# Ai-Camera.net
KiCad netlist of a schematic drawn in EasyEDA Pro
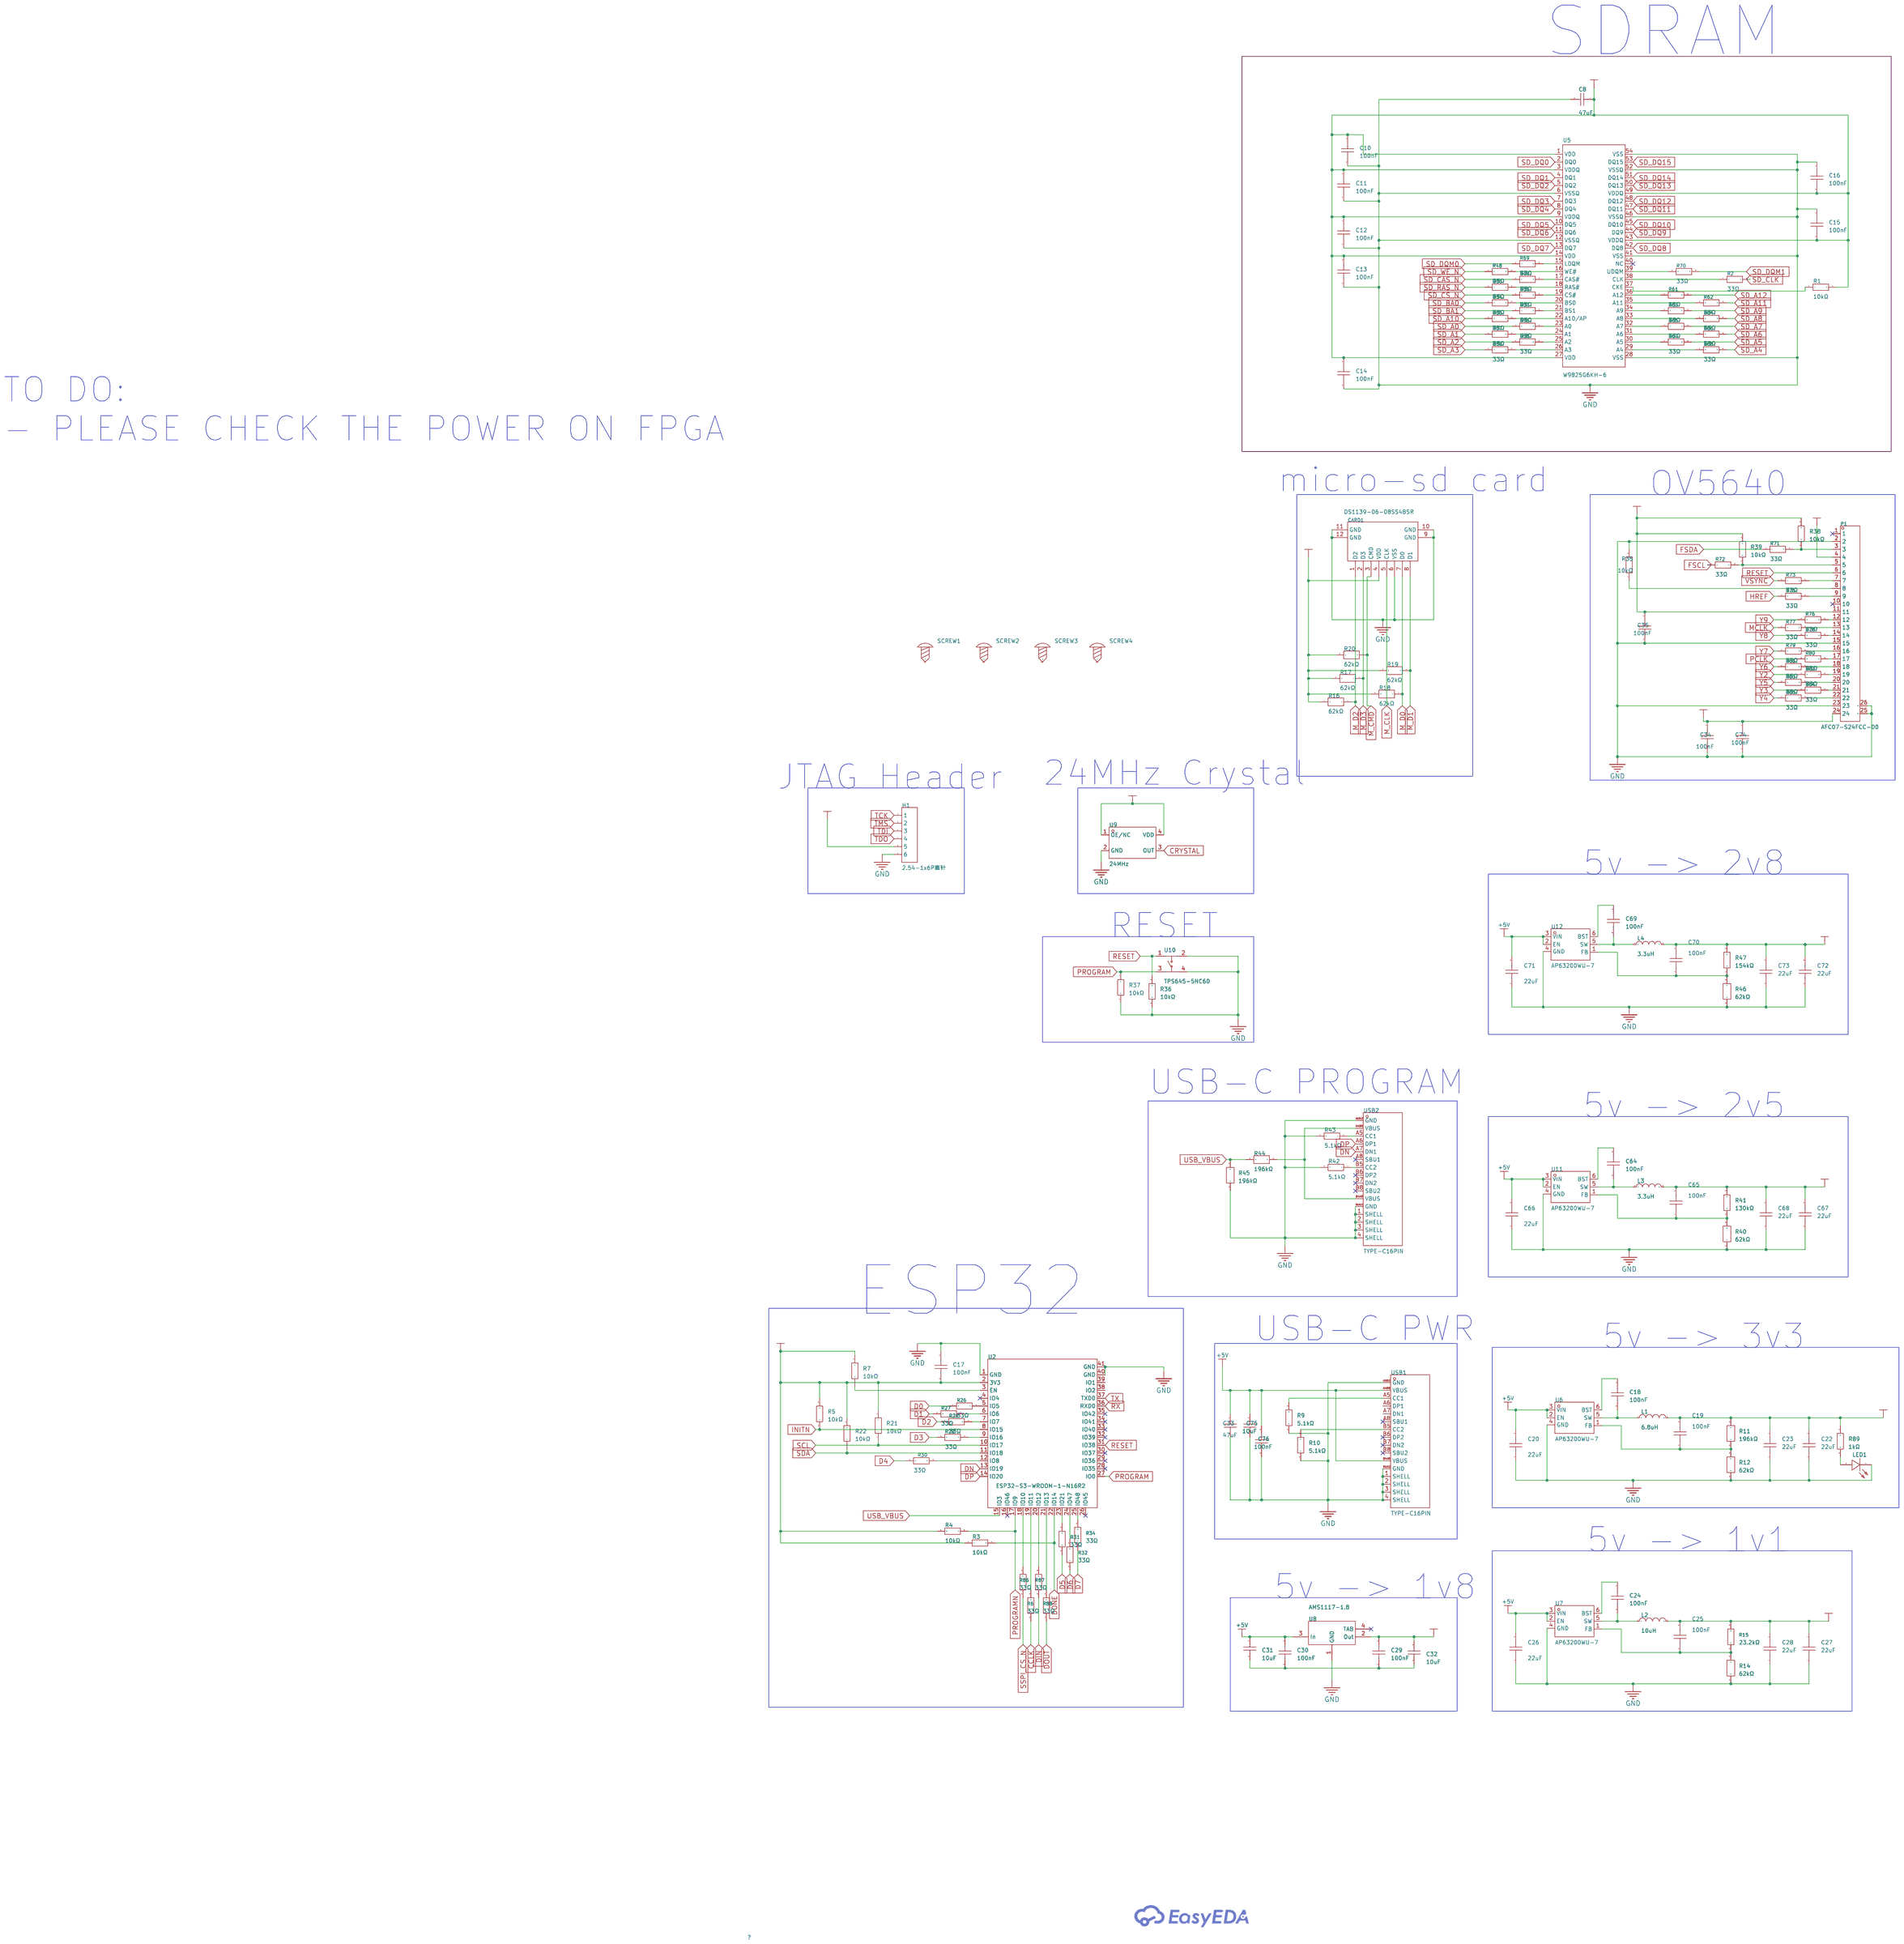
[diagram p0: P1]
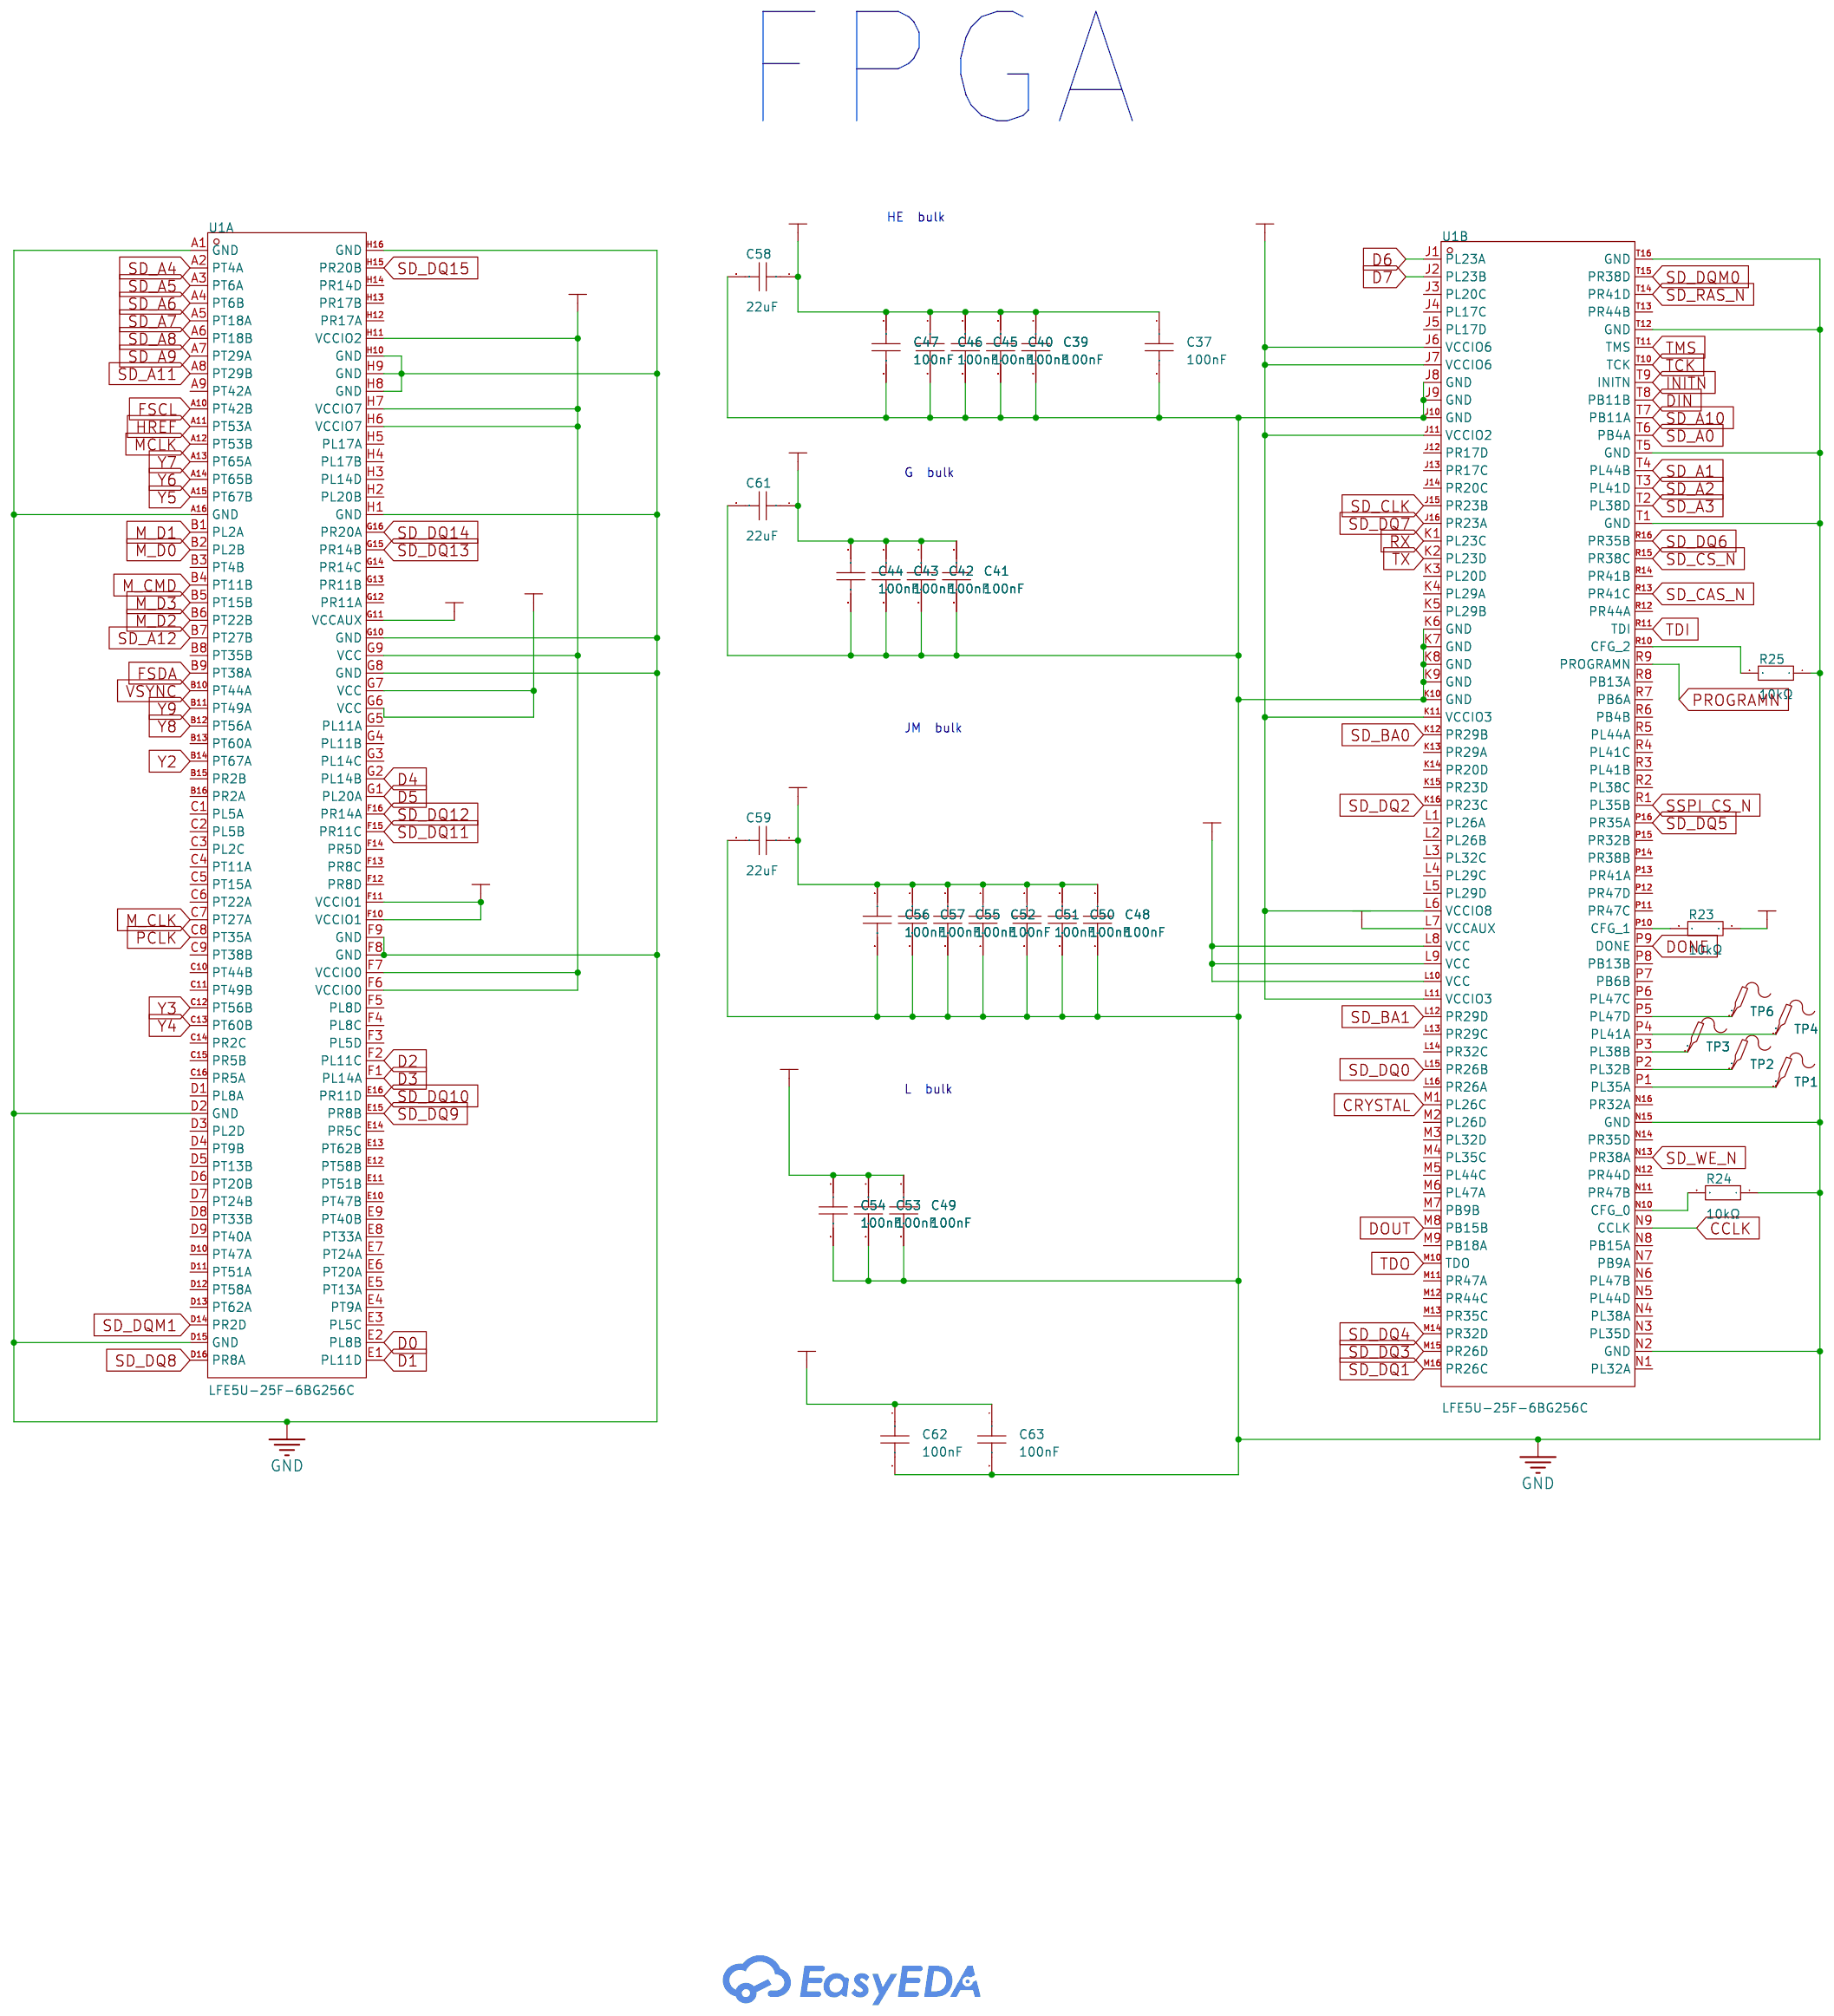
[diagram p1: FPGA]

(export (version "E")
  (design (tool "Eeschema 10.0.6"))
  (components
    (comp (ref "C8")
      (value "47uF")
      (footprint "easyedapro:C0805")
      (description "Capacitance:47uF Tolerance:±20% Tolerance:±20% Voltage Rating:6.3V Temperature Coefficient:X5R")
      (fields
        (field (name "Manufacturer Part") "CL21A476MQYNNNE")
        (field (name "Manufacturer") "SAMSUNG(三星)")
      )
      (libsource (lib "easyedapro") (part "CL21A476MQYNNNE"))
    )
    (comp (ref "C10")
      (value "100nF")
      (footprint "easyedapro:C01005")
      (description "Capacitance:100nF Tolerance:±10% Tolerance:±10% Voltage Rating:6.3V Temperature Coefficient:X5R")
      (fields
        (field (name "Manufacturer Part") "GRM022R60J104KE15D")
        (field (name "Manufacturer") "muRata(村田)")
      )
      (libsource (lib "easyedapro") (part "GRM022R60J104KE15D"))
    )
    (comp (ref "C11")
      (value "100nF")
      (footprint "easyedapro:C01005")
      (description "Capacitance:100nF Tolerance:±10% Tolerance:±10% Voltage Rating:6.3V Temperature Coefficient:X5R")
      (fields
        (field (name "Manufacturer Part") "GRM022R60J104KE15D")
        (field (name "Manufacturer") "muRata(村田)")
      )
      (libsource (lib "easyedapro") (part "GRM022R60J104KE15D"))
    )
    (comp (ref "C12")
      (value "100nF")
      (footprint "easyedapro:C01005")
      (description "Capacitance:100nF Tolerance:±10% Tolerance:±10% Voltage Rating:6.3V Temperature Coefficient:X5R")
      (fields
        (field (name "Manufacturer Part") "GRM022R60J104KE15D")
        (field (name "Manufacturer") "muRata(村田)")
      )
      (libsource (lib "easyedapro") (part "GRM022R60J104KE15D"))
    )
    (comp (ref "C13")
      (value "100nF")
      (footprint "easyedapro:C01005")
      (description "Capacitance:100nF Tolerance:±10% Tolerance:±10% Voltage Rating:6.3V Temperature Coefficient:X5R")
      (fields
        (field (name "Manufacturer Part") "GRM022R60J104KE15D")
        (field (name "Manufacturer") "muRata(村田)")
      )
      (libsource (lib "easyedapro") (part "GRM022R60J104KE15D"))
    )
    (comp (ref "C14")
      (value "100nF")
      (footprint "easyedapro:C01005")
      (description "Capacitance:100nF Tolerance:±10% Tolerance:±10% Voltage Rating:6.3V Temperature Coefficient:X5R")
      (fields
        (field (name "Manufacturer Part") "GRM022R60J104KE15D")
        (field (name "Manufacturer") "muRata(村田)")
      )
      (libsource (lib "easyedapro") (part "GRM022R60J104KE15D"))
    )
    (comp (ref "C15")
      (value "100nF")
      (footprint "easyedapro:C01005")
      (description "Capacitance:100nF Tolerance:±10% Tolerance:±10% Voltage Rating:6.3V Temperature Coefficient:X5R")
      (fields
        (field (name "Manufacturer Part") "GRM022R60J104KE15D")
        (field (name "Manufacturer") "muRata(村田)")
      )
      (libsource (lib "easyedapro") (part "GRM022R60J104KE15D"))
    )
    (comp (ref "C16")
      (value "100nF")
      (footprint "easyedapro:C01005")
      (description "Capacitance:100nF Tolerance:±10% Tolerance:±10% Voltage Rating:6.3V Temperature Coefficient:X5R")
      (fields
        (field (name "Manufacturer Part") "GRM022R60J104KE15D")
        (field (name "Manufacturer") "muRata(村田)")
      )
      (libsource (lib "easyedapro") (part "GRM022R60J104KE15D"))
    )
    (comp (ref "C17")
      (value "100nF")
      (footprint "easyedapro:C01005")
      (description "Capacitance:100nF Tolerance:±10% Tolerance:±10% Voltage Rating:6.3V Temperature Coefficient:X5R")
      (fields
        (field (name "Manufacturer Part") "GRM022R60J104KE15D")
        (field (name "Manufacturer") "muRata(村田)")
      )
      (libsource (lib "easyedapro") (part "GRM022R60J104KE15D"))
    )
    (comp (ref "C18")
      (value "100nF")
      (footprint "easyedapro:C01005")
      (description "Capacitance:100nF Tolerance:±10% Tolerance:±10% Voltage Rating:6.3V Temperature Coefficient:X5R")
      (fields
        (field (name "Manufacturer Part") "GRM022R60J104KE15D")
        (field (name "Manufacturer") "muRata(村田)")
      )
      (libsource (lib "easyedapro") (part "GRM022R60J104KE15D"))
    )
    (comp (ref "C19")
      (value "100nF")
      (footprint "easyedapro:C0603")
      (description "Capacitance:100nF Tolerance:±10% Tolerance:±10% Voltage Rating:50V Temperature Coefficient:X7R")
      (fields
        (field (name "Manufacturer Part") "TCC0603X7R104K500CT")
        (field (name "Manufacturer") "CCTC(三环)")
      )
      (libsource (lib "easyedapro") (part "TCC0603X7R104K500CT"))
    )
    (comp (ref "C20")
      (value "22uF")
      (footprint "easyedapro:C0603")
      (description "Capacitance:22uF Tolerance:±20% Tolerance:±20% Voltage Rating:6.3V Temperature Coefficient:X5R")
      (fields
        (field (name "Manufacturer Part") "TCC0603X5R226M6R3CT")
        (field (name "Manufacturer") "CCTC(三环)")
      )
      (libsource (lib "easyedapro") (part "TCC0603X5R226M6R3CT"))
    )
    (comp (ref "C22")
      (value "22uF")
      (footprint "easyedapro:C0603")
      (description "Capacitance:22uF Tolerance:±20% Tolerance:±20% Voltage Rating:6.3V Temperature Coefficient:X5R")
      (fields
        (field (name "Manufacturer Part") "TCC0603X5R226M6R3CT")
        (field (name "Manufacturer") "CCTC(三环)")
      )
      (libsource (lib "easyedapro") (part "TCC0603X5R226M6R3CT"))
    )
    (comp (ref "C23")
      (value "22uF")
      (footprint "easyedapro:C0603")
      (description "Capacitance:22uF Tolerance:±20% Tolerance:±20% Voltage Rating:6.3V Temperature Coefficient:X5R")
      (fields
        (field (name "Manufacturer Part") "TCC0603X5R226M6R3CT")
        (field (name "Manufacturer") "CCTC(三环)")
      )
      (libsource (lib "easyedapro") (part "TCC0603X5R226M6R3CT"))
    )
    (comp (ref "C24")
      (value "100nF")
      (footprint "easyedapro:C01005")
      (description "Capacitance:100nF Tolerance:±10% Tolerance:±10% Voltage Rating:6.3V Temperature Coefficient:X5R")
      (fields
        (field (name "Manufacturer Part") "GRM022R60J104KE15D")
        (field (name "Manufacturer") "muRata(村田)")
      )
      (libsource (lib "easyedapro") (part "GRM022R60J104KE15D"))
    )
    (comp (ref "C25")
      (value "100nF")
      (footprint "easyedapro:C0603")
      (description "Capacitance:100nF Tolerance:±10% Tolerance:±10% Voltage Rating:50V Temperature Coefficient:X7R")
      (fields
        (field (name "Manufacturer Part") "TCC0603X7R104K500CT")
        (field (name "Manufacturer") "CCTC(三环)")
      )
      (libsource (lib "easyedapro") (part "TCC0603X7R104K500CT"))
    )
    (comp (ref "C26")
      (value "22uF")
      (footprint "easyedapro:C0603")
      (description "Capacitance:22uF Tolerance:±20% Tolerance:±20% Voltage Rating:6.3V Temperature Coefficient:X5R")
      (fields
        (field (name "Manufacturer Part") "TCC0603X5R226M6R3CT")
        (field (name "Manufacturer") "CCTC(三环)")
      )
      (libsource (lib "easyedapro") (part "TCC0603X5R226M6R3CT"))
    )
    (comp (ref "C27")
      (value "22uF")
      (footprint "easyedapro:C0603")
      (description "Capacitance:22uF Tolerance:±20% Tolerance:±20% Voltage Rating:6.3V Temperature Coefficient:X5R")
      (fields
        (field (name "Manufacturer Part") "TCC0603X5R226M6R3CT")
        (field (name "Manufacturer") "CCTC(三环)")
      )
      (libsource (lib "easyedapro") (part "TCC0603X5R226M6R3CT"))
    )
    (comp (ref "C28")
      (value "22uF")
      (footprint "easyedapro:C0603")
      (description "Capacitance:22uF Tolerance:±20% Tolerance:±20% Voltage Rating:6.3V Temperature Coefficient:X5R")
      (fields
        (field (name "Manufacturer Part") "TCC0603X5R226M6R3CT")
        (field (name "Manufacturer") "CCTC(三环)")
      )
      (libsource (lib "easyedapro") (part "TCC0603X5R226M6R3CT"))
    )
    (comp (ref "C29")
      (value "100nF")
      (footprint "easyedapro:C01005")
      (description "Capacitance:100nF Tolerance:±10% Tolerance:±10% Voltage Rating:6.3V Temperature Coefficient:X5R")
      (fields
        (field (name "Manufacturer Part") "GRM022R60J104KE15D")
        (field (name "Manufacturer") "muRata(村田)")
      )
      (libsource (lib "easyedapro") (part "GRM022R60J104KE15D"))
    )
    (comp (ref "C30")
      (value "100nF")
      (footprint "easyedapro:C01005")
      (description "Capacitance:100nF Tolerance:±10% Tolerance:±10% Voltage Rating:6.3V Temperature Coefficient:X5R")
      (fields
        (field (name "Manufacturer Part") "GRM022R60J104KE15D")
        (field (name "Manufacturer") "muRata(村田)")
      )
      (libsource (lib "easyedapro") (part "GRM022R60J104KE15D"))
    )
    (comp (ref "C31")
      (value "10uF")
      (footprint "easyedapro:C0402")
      (description "Capacitance:10uF Tolerance:±20% Tolerance:±20% Voltage Rating:6.3V Temperature Coefficient:X5R")
      (fields
        (field (name "Manufacturer Part") "GRM155R60J106ME44D")
        (field (name "Manufacturer") "muRata(村田)")
      )
      (libsource (lib "easyedapro") (part "GRM155R60J106ME44D"))
    )
    (comp (ref "C32")
      (value "10uF")
      (footprint "easyedapro:C0402")
      (description "Capacitance:10uF Tolerance:±20% Tolerance:±20% Voltage Rating:6.3V Temperature Coefficient:X5R")
      (fields
        (field (name "Manufacturer Part") "GRM155R60J106ME44D")
        (field (name "Manufacturer") "muRata(村田)")
      )
      (libsource (lib "easyedapro") (part "GRM155R60J106ME44D"))
    )
    (comp (ref "C33")
      (value "47uF")
      (footprint "easyedapro:C0805")
      (description "Capacitance:47uF Tolerance:±20% Tolerance:±20% Voltage Rating:6.3V Temperature Coefficient:X5R")
      (fields
        (field (name "Manufacturer Part") "CL21A476MQYNNNE")
        (field (name "Manufacturer") "SAMSUNG(三星)")
      )
      (libsource (lib "easyedapro") (part "CL21A476MQYNNNE"))
    )
    (comp (ref "C34")
      (value "100nF")
      (footprint "easyedapro:C01005")
      (description "Capacitance:100nF Tolerance:±10% Tolerance:±10% Voltage Rating:6.3V Temperature Coefficient:X5R")
      (fields
        (field (name "Manufacturer Part") "GRM022R60J104KE15D")
        (field (name "Manufacturer") "muRata(村田)")
      )
      (libsource (lib "easyedapro") (part "GRM022R60J104KE15D"))
    )
    (comp (ref "C35")
      (value "100nF")
      (footprint "easyedapro:C01005")
      (description "Capacitance:100nF Tolerance:±10% Tolerance:±10% Voltage Rating:6.3V Temperature Coefficient:X5R")
      (fields
        (field (name "Manufacturer Part") "GRM022R60J104KE15D")
        (field (name "Manufacturer") "muRata(村田)")
      )
      (libsource (lib "easyedapro") (part "GRM022R60J104KE15D"))
    )
    (comp (ref "C64")
      (value "100nF")
      (footprint "easyedapro:C01005")
      (description "Capacitance:100nF Tolerance:±10% Tolerance:±10% Voltage Rating:6.3V Temperature Coefficient:X5R")
      (fields
        (field (name "Manufacturer Part") "GRM022R60J104KE15D")
        (field (name "Manufacturer") "muRata(村田)")
      )
      (libsource (lib "easyedapro") (part "GRM022R60J104KE15D"))
    )
    (comp (ref "C65")
      (value "100nF")
      (footprint "easyedapro:C0603")
      (description "Capacitance:100nF Tolerance:±10% Tolerance:±10% Voltage Rating:50V Temperature Coefficient:X7R")
      (fields
        (field (name "Manufacturer Part") "TCC0603X7R104K500CT")
        (field (name "Manufacturer") "CCTC(三环)")
      )
      (libsource (lib "easyedapro") (part "TCC0603X7R104K500CT"))
    )
    (comp (ref "C66")
      (value "22uF")
      (footprint "easyedapro:C0603")
      (description "Capacitance:22uF Tolerance:±20% Tolerance:±20% Voltage Rating:6.3V Temperature Coefficient:X5R")
      (fields
        (field (name "Manufacturer Part") "TCC0603X5R226M6R3CT")
        (field (name "Manufacturer") "CCTC(三环)")
      )
      (libsource (lib "easyedapro") (part "TCC0603X5R226M6R3CT"))
    )
    (comp (ref "C67")
      (value "22uF")
      (footprint "easyedapro:C0603")
      (description "Capacitance:22uF Tolerance:±20% Tolerance:±20% Voltage Rating:6.3V Temperature Coefficient:X5R")
      (fields
        (field (name "Manufacturer Part") "TCC0603X5R226M6R3CT")
        (field (name "Manufacturer") "CCTC(三环)")
      )
      (libsource (lib "easyedapro") (part "TCC0603X5R226M6R3CT"))
    )
    (comp (ref "C68")
      (value "22uF")
      (footprint "easyedapro:C0603")
      (description "Capacitance:22uF Tolerance:±20% Tolerance:±20% Voltage Rating:6.3V Temperature Coefficient:X5R")
      (fields
        (field (name "Manufacturer Part") "TCC0603X5R226M6R3CT")
        (field (name "Manufacturer") "CCTC(三环)")
      )
      (libsource (lib "easyedapro") (part "TCC0603X5R226M6R3CT"))
    )
    (comp (ref "C69")
      (value "100nF")
      (footprint "easyedapro:C01005")
      (description "Capacitance:100nF Tolerance:±10% Tolerance:±10% Voltage Rating:6.3V Temperature Coefficient:X5R")
      (fields
        (field (name "Manufacturer Part") "GRM022R60J104KE15D")
        (field (name "Manufacturer") "muRata(村田)")
      )
      (libsource (lib "easyedapro") (part "GRM022R60J104KE15D"))
    )
    (comp (ref "C70")
      (value "100nF")
      (footprint "easyedapro:C0603")
      (description "Capacitance:100nF Tolerance:±10% Tolerance:±10% Voltage Rating:50V Temperature Coefficient:X7R")
      (fields
        (field (name "Manufacturer Part") "TCC0603X7R104K500CT")
        (field (name "Manufacturer") "CCTC(三环)")
      )
      (libsource (lib "easyedapro") (part "TCC0603X7R104K500CT"))
    )
    (comp (ref "C71")
      (value "22uF")
      (footprint "easyedapro:C0603")
      (description "Capacitance:22uF Tolerance:±20% Tolerance:±20% Voltage Rating:6.3V Temperature Coefficient:X5R")
      (fields
        (field (name "Manufacturer Part") "TCC0603X5R226M6R3CT")
        (field (name "Manufacturer") "CCTC(三环)")
      )
      (libsource (lib "easyedapro") (part "TCC0603X5R226M6R3CT"))
    )
    (comp (ref "C72")
      (value "22uF")
      (footprint "easyedapro:C0603")
      (description "Capacitance:22uF Tolerance:±20% Tolerance:±20% Voltage Rating:6.3V Temperature Coefficient:X5R")
      (fields
        (field (name "Manufacturer Part") "TCC0603X5R226M6R3CT")
        (field (name "Manufacturer") "CCTC(三环)")
      )
      (libsource (lib "easyedapro") (part "TCC0603X5R226M6R3CT"))
    )
    (comp (ref "C73")
      (value "22uF")
      (footprint "easyedapro:C0603")
      (description "Capacitance:22uF Tolerance:±20% Tolerance:±20% Voltage Rating:6.3V Temperature Coefficient:X5R")
      (fields
        (field (name "Manufacturer Part") "TCC0603X5R226M6R3CT")
        (field (name "Manufacturer") "CCTC(三环)")
      )
      (libsource (lib "easyedapro") (part "TCC0603X5R226M6R3CT"))
    )
    (comp (ref "C74")
      (value "100nF")
      (footprint "easyedapro:C01005")
      (description "Capacitance:100nF Tolerance:±10% Tolerance:±10% Voltage Rating:6.3V Temperature Coefficient:X5R")
      (fields
        (field (name "Manufacturer Part") "GRM022R60J104KE15D")
        (field (name "Manufacturer") "muRata(村田)")
      )
      (libsource (lib "easyedapro") (part "GRM022R60J104KE15D"))
    )
    (comp (ref "C75")
      (value "10uF")
      (footprint "easyedapro:C0402")
      (description "Capacitance:10uF Tolerance:±20% Tolerance:±20% Voltage Rating:6.3V Temperature Coefficient:X5R")
      (fields
        (field (name "Manufacturer Part") "GRM155R60J106ME44D")
        (field (name "Manufacturer") "muRata(村田)")
      )
      (libsource (lib "easyedapro") (part "GRM155R60J106ME44D"))
    )
    (comp (ref "C76")
      (value "100nF")
      (footprint "easyedapro:C01005")
      (description "Capacitance:100nF Tolerance:±10% Tolerance:±10% Voltage Rating:6.3V Temperature Coefficient:X5R")
      (fields
        (field (name "Manufacturer Part") "GRM022R60J104KE15D")
        (field (name "Manufacturer") "muRata(村田)")
      )
      (libsource (lib "easyedapro") (part "GRM022R60J104KE15D"))
    )
    (comp (ref "CARD1")
      (value "DS1139-06-08SS4BSR")
      (footprint "easyedapro:TF-SMD_DS1139-06-08SS4BSR")
      (fields (field (name "Manufacturer") "CONNFLY"))
      (libsource (lib "easyedapro") (part "DS1139-06-08SS4BSR"))
    )
    (comp (ref "H1")
      (value "2.54-1x6P直针")
      (footprint "easyedapro:HDR-TH_6P-P2.54-V-M-1")
      (fields (field (name "Manufacturer") "BOOMELE(博穆精密)"))
      (libsource (lib "easyedapro") (part "Header-Male-2.54_1x6"))
    )
    (comp (ref "L1")
      (value "6.8uH")
      (footprint "easyedapro:IND-SMD_L7.0-W6.6")
      (fields (field (name "Manufacturer Part") "FXL0630-6R8-M") (field (name "Manufacturer") "cjiang(长江微电)"))
      (libsource (lib "easyedapro") (part "FXL0630-6R8-M"))
    )
    (comp (ref "L2")
      (value "10uH")
      (footprint "easyedapro:IND-SMD_L7.3-W6.8")
      (fields (field (name "Manufacturer Part") "FXL0630-100-M") (field (name "Manufacturer") "cjiang(长江微电)"))
      (libsource (lib "easyedapro") (part "FXL0630-100-M"))
    )
    (comp (ref "L3")
      (value "3.3uH")
      (footprint "easyedapro:IND-SMD_L4.5-W4.1_SL0420")
      (description "Inductance:3.3uH Tolerance:±20% Tolerance:±20% Current Rating:3.5A Current - Saturation (Isat):4A")
      (fields (field (name "Manufacturer Part") "SL0420-3R3M") (field (name "Manufacturer") "台湾陆海"))
      (libsource (lib "easyedapro") (part "SL0420-3R3M"))
    )
    (comp (ref "L4")
      (value "3.3uH")
      (footprint "easyedapro:IND-SMD_L4.5-W4.1_SL0420")
      (description "Inductance:3.3uH Tolerance:±20% Tolerance:±20% Current Rating:3.5A Current - Saturation (Isat):4A")
      (fields (field (name "Manufacturer Part") "SL0420-3R3M") (field (name "Manufacturer") "台湾陆海"))
      (libsource (lib "easyedapro") (part "SL0420-3R3M"))
    )
    (comp (ref "LED1")
      (value "~")
      (footprint "easyedapro:LED0805-RD_RED")
      (description "Emitted Color:红灯")
      (fields (field (name "Manufacturer Part") "NCD0805R1") (field (name "Manufacturer") "国星光电"))
      (libsource (lib "easyedapro") (part "FC-2012HRK-620D"))
    )
    (comp (ref "P1")
      (value "AFC07-S24FCC-00")
      (footprint "easyedapro:FPC-SMD_AFC07-S24FCC-00")
      (fields (field (name "Manufacturer") "JS(钜硕电子)"))
      (libsource (lib "easyedapro") (part "FPC 0.5MM 24P Pull type H2.0mm Under the next"))
    )
    (comp (ref "R1")
      (value "10kΩ")
      (footprint "easyedapro:R0402")
      (fields
        (field (name "Manufacturer Part") "0402WGF1002TCE")
        (field (name "Manufacturer") "UNI-ROYAL(厚声)")
      )
      (libsource (lib "easyedapro") (part "0402WGF1002TCE"))
    )
    (comp (ref "R2")
      (value "33Ω")
      (footprint "easyedapro:R0402")
      (fields
        (field (name "Manufacturer Part") "0402WGF330JTCE")
        (field (name "Manufacturer") "UNI-ROYAL(厚声)")
      )
      (libsource (lib "easyedapro") (part "0402WGF330JTCE"))
    )
    (comp (ref "R3")
      (value "10kΩ")
      (footprint "easyedapro:R0402")
      (fields
        (field (name "Manufacturer Part") "0402WGF1002TCE")
        (field (name "Manufacturer") "UNI-ROYAL(厚声)")
      )
      (libsource (lib "easyedapro") (part "0402WGF1002TCE"))
    )
    (comp (ref "R4")
      (value "10kΩ")
      (footprint "easyedapro:R0402")
      (fields
        (field (name "Manufacturer Part") "0402WGF1002TCE")
        (field (name "Manufacturer") "UNI-ROYAL(厚声)")
      )
      (libsource (lib "easyedapro") (part "0402WGF1002TCE"))
    )
    (comp (ref "R5")
      (value "10kΩ")
      (footprint "easyedapro:R0402")
      (fields
        (field (name "Manufacturer Part") "0402WGF1002TCE")
        (field (name "Manufacturer") "UNI-ROYAL(厚声)")
      )
      (libsource (lib "easyedapro") (part "0402WGF1002TCE"))
    )
    (comp (ref "R6")
      (value "33Ω")
      (footprint "easyedapro:R0402")
      (fields
        (field (name "Manufacturer Part") "0402WGF330JTCE")
        (field (name "Manufacturer") "UNI-ROYAL(厚声)")
      )
      (libsource (lib "easyedapro") (part "0402WGF330JTCE"))
    )
    (comp (ref "R7")
      (value "10kΩ")
      (footprint "easyedapro:R0402")
      (fields
        (field (name "Manufacturer Part") "0402WGF1002TCE")
        (field (name "Manufacturer") "UNI-ROYAL(厚声)")
      )
      (libsource (lib "easyedapro") (part "0402WGF1002TCE"))
    )
    (comp (ref "R9")
      (value "5.1kΩ")
      (footprint "easyedapro:R0603")
      (fields
        (field (name "Manufacturer Part") "0603WAF5101T5E")
        (field (name "Manufacturer") "UNI-ROYAL(厚声)")
      )
      (libsource (lib "easyedapro") (part "0603WAF5101T5E"))
    )
    (comp (ref "R10")
      (value "5.1kΩ")
      (footprint "easyedapro:R0603")
      (fields
        (field (name "Manufacturer Part") "0603WAF5101T5E")
        (field (name "Manufacturer") "UNI-ROYAL(厚声)")
      )
      (libsource (lib "easyedapro") (part "0603WAF5101T5E"))
    )
    (comp (ref "R11")
      (value "196kΩ")
      (footprint "easyedapro:R0603")
      (fields (field (name "Manufacturer Part") "FRC0603F1963TS") (field (name "Manufacturer") "FOJAN(富捷)"))
      (libsource (lib "easyedapro") (part "FRC0603F1963TS"))
    )
    (comp (ref "R12")
      (value "62kΩ")
      (footprint "easyedapro:R0603")
      (fields (field (name "Manufacturer Part") "FRC0603F6202TS") (field (name "Manufacturer") "FOJAN(富捷)"))
      (libsource (lib "easyedapro") (part "FRC0603F6202TS"))
    )
    (comp (ref "R14")
      (value "62kΩ")
      (footprint "easyedapro:R0603")
      (fields (field (name "Manufacturer Part") "FRC0603F6202TS") (field (name "Manufacturer") "FOJAN(富捷)"))
      (libsource (lib "easyedapro") (part "FRC0603F6202TS"))
    )
    (comp (ref "R15")
      (value "23.2kΩ")
      (footprint "easyedapro:R0603")
      (fields
        (field (name "Manufacturer Part") "0603WAF2322T5E")
        (field (name "Manufacturer") "UNI-ROYAL(厚声)")
      )
      (libsource (lib "easyedapro") (part "0603WAF2322T5E"))
    )
    (comp (ref "R16")
      (value "62kΩ")
      (footprint "easyedapro:R0603")
      (fields (field (name "Manufacturer Part") "FRC0603F6202TS") (field (name "Manufacturer") "FOJAN(富捷)"))
      (libsource (lib "easyedapro") (part "FRC0603F6202TS"))
    )
    (comp (ref "R17")
      (value "62kΩ")
      (footprint "easyedapro:R0603")
      (fields (field (name "Manufacturer Part") "FRC0603F6202TS") (field (name "Manufacturer") "FOJAN(富捷)"))
      (libsource (lib "easyedapro") (part "FRC0603F6202TS"))
    )
    (comp (ref "R18")
      (value "62kΩ")
      (footprint "easyedapro:R0603")
      (fields (field (name "Manufacturer Part") "FRC0603F6202TS") (field (name "Manufacturer") "FOJAN(富捷)"))
      (libsource (lib "easyedapro") (part "FRC0603F6202TS"))
    )
    (comp (ref "R19")
      (value "62kΩ")
      (footprint "easyedapro:R0603")
      (fields (field (name "Manufacturer Part") "FRC0603F6202TS") (field (name "Manufacturer") "FOJAN(富捷)"))
      (libsource (lib "easyedapro") (part "FRC0603F6202TS"))
    )
    (comp (ref "R20")
      (value "62kΩ")
      (footprint "easyedapro:R0603")
      (fields (field (name "Manufacturer Part") "FRC0603F6202TS") (field (name "Manufacturer") "FOJAN(富捷)"))
      (libsource (lib "easyedapro") (part "FRC0603F6202TS"))
    )
    (comp (ref "R21")
      (value "10kΩ")
      (footprint "easyedapro:R0402")
      (fields
        (field (name "Manufacturer Part") "0402WGF1002TCE")
        (field (name "Manufacturer") "UNI-ROYAL(厚声)")
      )
      (libsource (lib "easyedapro") (part "0402WGF1002TCE"))
    )
    (comp (ref "R22")
      (value "10kΩ")
      (footprint "easyedapro:R0402")
      (fields
        (field (name "Manufacturer Part") "0402WGF1002TCE")
        (field (name "Manufacturer") "UNI-ROYAL(厚声)")
      )
      (libsource (lib "easyedapro") (part "0402WGF1002TCE"))
    )
    (comp (ref "R26")
      (value "33Ω")
      (footprint "easyedapro:R0402")
      (fields
        (field (name "Manufacturer Part") "0402WGF330JTCE")
        (field (name "Manufacturer") "UNI-ROYAL(厚声)")
      )
      (libsource (lib "easyedapro") (part "0402WGF330JTCE"))
    )
    (comp (ref "R27")
      (value "33Ω")
      (footprint "easyedapro:R0402")
      (fields
        (field (name "Manufacturer Part") "0402WGF330JTCE")
        (field (name "Manufacturer") "UNI-ROYAL(厚声)")
      )
      (libsource (lib "easyedapro") (part "0402WGF330JTCE"))
    )
    (comp (ref "R28")
      (value "33Ω")
      (footprint "easyedapro:R0402")
      (fields
        (field (name "Manufacturer Part") "0402WGF330JTCE")
        (field (name "Manufacturer") "UNI-ROYAL(厚声)")
      )
      (libsource (lib "easyedapro") (part "0402WGF330JTCE"))
    )
    (comp (ref "R29")
      (value "33Ω")
      (footprint "easyedapro:R0402")
      (fields
        (field (name "Manufacturer Part") "0402WGF330JTCE")
        (field (name "Manufacturer") "UNI-ROYAL(厚声)")
      )
      (libsource (lib "easyedapro") (part "0402WGF330JTCE"))
    )
    (comp (ref "R30")
      (value "33Ω")
      (footprint "easyedapro:R0402")
      (fields
        (field (name "Manufacturer Part") "0402WGF330JTCE")
        (field (name "Manufacturer") "UNI-ROYAL(厚声)")
      )
      (libsource (lib "easyedapro") (part "0402WGF330JTCE"))
    )
    (comp (ref "R31")
      (value "33Ω")
      (footprint "easyedapro:R0402")
      (fields
        (field (name "Manufacturer Part") "0402WGF330JTCE")
        (field (name "Manufacturer") "UNI-ROYAL(厚声)")
      )
      (libsource (lib "easyedapro") (part "0402WGF330JTCE"))
    )
    (comp (ref "R32")
      (value "33Ω")
      (footprint "easyedapro:R0402")
      (fields
        (field (name "Manufacturer Part") "0402WGF330JTCE")
        (field (name "Manufacturer") "UNI-ROYAL(厚声)")
      )
      (libsource (lib "easyedapro") (part "0402WGF330JTCE"))
    )
    (comp (ref "R34")
      (value "33Ω")
      (footprint "easyedapro:R0402")
      (fields
        (field (name "Manufacturer Part") "0402WGF330JTCE")
        (field (name "Manufacturer") "UNI-ROYAL(厚声)")
      )
      (libsource (lib "easyedapro") (part "0402WGF330JTCE"))
    )
    (comp (ref "R35")
      (value "10kΩ")
      (footprint "easyedapro:R0402")
      (fields
        (field (name "Manufacturer Part") "0402WGF1002TCE")
        (field (name "Manufacturer") "UNI-ROYAL(厚声)")
      )
      (libsource (lib "easyedapro") (part "0402WGF1002TCE"))
    )
    (comp (ref "R36")
      (value "10kΩ")
      (footprint "easyedapro:R0402")
      (fields
        (field (name "Manufacturer Part") "0402WGF1002TCE")
        (field (name "Manufacturer") "UNI-ROYAL(厚声)")
      )
      (libsource (lib "easyedapro") (part "0402WGF1002TCE"))
    )
    (comp (ref "R37")
      (value "10kΩ")
      (footprint "easyedapro:R0402")
      (fields
        (field (name "Manufacturer Part") "0402WGF1002TCE")
        (field (name "Manufacturer") "UNI-ROYAL(厚声)")
      )
      (libsource (lib "easyedapro") (part "0402WGF1002TCE"))
    )
    (comp (ref "R38")
      (value "10kΩ")
      (footprint "easyedapro:R0402")
      (fields
        (field (name "Manufacturer Part") "0402WGF1002TCE")
        (field (name "Manufacturer") "UNI-ROYAL(厚声)")
      )
      (libsource (lib "easyedapro") (part "0402WGF1002TCE"))
    )
    (comp (ref "R39")
      (value "10kΩ")
      (footprint "easyedapro:R0402")
      (fields
        (field (name "Manufacturer Part") "0402WGF1002TCE")
        (field (name "Manufacturer") "UNI-ROYAL(厚声)")
      )
      (libsource (lib "easyedapro") (part "0402WGF1002TCE"))
    )
    (comp (ref "R40")
      (value "62kΩ")
      (footprint "easyedapro:R0603")
      (fields (field (name "Manufacturer Part") "FRC0603F6202TS") (field (name "Manufacturer") "FOJAN(富捷)"))
      (libsource (lib "easyedapro") (part "FRC0603F6202TS"))
    )
    (comp (ref "R41")
      (value "130kΩ")
      (footprint "easyedapro:R0402")
      (fields (field (name "Manufacturer Part") "RC0402FR-07130KL") (field (name "Manufacturer") "YAGEO(国巨)"))
      (libsource (lib "easyedapro") (part "RC0402FR-07130KL"))
    )
    (comp (ref "R42")
      (value "5.1kΩ")
      (footprint "easyedapro:R0603")
      (fields
        (field (name "Manufacturer Part") "0603WAF5101T5E")
        (field (name "Manufacturer") "UNI-ROYAL(厚声)")
      )
      (libsource (lib "easyedapro") (part "0603WAF5101T5E"))
    )
    (comp (ref "R43")
      (value "5.1kΩ")
      (footprint "easyedapro:R0603")
      (fields
        (field (name "Manufacturer Part") "0603WAF5101T5E")
        (field (name "Manufacturer") "UNI-ROYAL(厚声)")
      )
      (libsource (lib "easyedapro") (part "0603WAF5101T5E"))
    )
    (comp (ref "R44")
      (value "196kΩ")
      (footprint "easyedapro:R0603")
      (fields (field (name "Manufacturer Part") "FRC0603F1963TS") (field (name "Manufacturer") "FOJAN(富捷)"))
      (libsource (lib "easyedapro") (part "FRC0603F1963TS"))
    )
    (comp (ref "R45")
      (value "196kΩ")
      (footprint "easyedapro:R0603")
      (fields (field (name "Manufacturer Part") "FRC0603F1963TS") (field (name "Manufacturer") "FOJAN(富捷)"))
      (libsource (lib "easyedapro") (part "FRC0603F1963TS"))
    )
    (comp (ref "R46")
      (value "62kΩ")
      (footprint "easyedapro:R0603")
      (fields (field (name "Manufacturer Part") "FRC0603F6202TS") (field (name "Manufacturer") "FOJAN(富捷)"))
      (libsource (lib "easyedapro") (part "FRC0603F6202TS"))
    )
    (comp (ref "R47")
      (value "154kΩ")
      (footprint "easyedapro:R0402")
      (fields
        (field (name "Manufacturer Part") "0402WGF1543TCE")
        (field (name "Manufacturer") "UNI-ROYAL(厚声)")
      )
      (libsource (lib "easyedapro") (part "0402WGF1543TCE"))
    )
    (comp (ref "R48")
      (value "33Ω")
      (footprint "easyedapro:R0402")
      (fields
        (field (name "Manufacturer Part") "0402WGF330JTCE")
        (field (name "Manufacturer") "UNI-ROYAL(厚声)")
      )
      (libsource (lib "easyedapro") (part "0402WGF330JTCE"))
    )
    (comp (ref "R49")
      (value "33Ω")
      (footprint "easyedapro:R0402")
      (fields
        (field (name "Manufacturer Part") "0402WGF330JTCE")
        (field (name "Manufacturer") "UNI-ROYAL(厚声)")
      )
      (libsource (lib "easyedapro") (part "0402WGF330JTCE"))
    )
    (comp (ref "R50")
      (value "33Ω")
      (footprint "easyedapro:R0402")
      (fields
        (field (name "Manufacturer Part") "0402WGF330JTCE")
        (field (name "Manufacturer") "UNI-ROYAL(厚声)")
      )
      (libsource (lib "easyedapro") (part "0402WGF330JTCE"))
    )
    (comp (ref "R51")
      (value "33Ω")
      (footprint "easyedapro:R0402")
      (fields
        (field (name "Manufacturer Part") "0402WGF330JTCE")
        (field (name "Manufacturer") "UNI-ROYAL(厚声)")
      )
      (libsource (lib "easyedapro") (part "0402WGF330JTCE"))
    )
    (comp (ref "R53")
      (value "33Ω")
      (footprint "easyedapro:R0402")
      (fields
        (field (name "Manufacturer Part") "0402WGF330JTCE")
        (field (name "Manufacturer") "UNI-ROYAL(厚声)")
      )
      (libsource (lib "easyedapro") (part "0402WGF330JTCE"))
    )
    (comp (ref "R54")
      (value "33Ω")
      (footprint "easyedapro:R0402")
      (fields
        (field (name "Manufacturer Part") "0402WGF330JTCE")
        (field (name "Manufacturer") "UNI-ROYAL(厚声)")
      )
      (libsource (lib "easyedapro") (part "0402WGF330JTCE"))
    )
    (comp (ref "R55")
      (value "33Ω")
      (footprint "easyedapro:R0402")
      (fields
        (field (name "Manufacturer Part") "0402WGF330JTCE")
        (field (name "Manufacturer") "UNI-ROYAL(厚声)")
      )
      (libsource (lib "easyedapro") (part "0402WGF330JTCE"))
    )
    (comp (ref "R56")
      (value "33Ω")
      (footprint "easyedapro:R0402")
      (fields
        (field (name "Manufacturer Part") "0402WGF330JTCE")
        (field (name "Manufacturer") "UNI-ROYAL(厚声)")
      )
      (libsource (lib "easyedapro") (part "0402WGF330JTCE"))
    )
    (comp (ref "R57")
      (value "33Ω")
      (footprint "easyedapro:R0402")
      (fields
        (field (name "Manufacturer Part") "0402WGF330JTCE")
        (field (name "Manufacturer") "UNI-ROYAL(厚声)")
      )
      (libsource (lib "easyedapro") (part "0402WGF330JTCE"))
    )
    (comp (ref "R58")
      (value "33Ω")
      (footprint "easyedapro:R0402")
      (fields
        (field (name "Manufacturer Part") "0402WGF330JTCE")
        (field (name "Manufacturer") "UNI-ROYAL(厚声)")
      )
      (libsource (lib "easyedapro") (part "0402WGF330JTCE"))
    )
    (comp (ref "R59")
      (value "33Ω")
      (footprint "easyedapro:R0402")
      (fields
        (field (name "Manufacturer Part") "0402WGF330JTCE")
        (field (name "Manufacturer") "UNI-ROYAL(厚声)")
      )
      (libsource (lib "easyedapro") (part "0402WGF330JTCE"))
    )
    (comp (ref "R61")
      (value "33Ω")
      (footprint "easyedapro:R0402")
      (fields
        (field (name "Manufacturer Part") "0402WGF330JTCE")
        (field (name "Manufacturer") "UNI-ROYAL(厚声)")
      )
      (libsource (lib "easyedapro") (part "0402WGF330JTCE"))
    )
    (comp (ref "R62")
      (value "33Ω")
      (footprint "easyedapro:R0402")
      (fields
        (field (name "Manufacturer Part") "0402WGF330JTCE")
        (field (name "Manufacturer") "UNI-ROYAL(厚声)")
      )
      (libsource (lib "easyedapro") (part "0402WGF330JTCE"))
    )
    (comp (ref "R63")
      (value "33Ω")
      (footprint "easyedapro:R0402")
      (fields
        (field (name "Manufacturer Part") "0402WGF330JTCE")
        (field (name "Manufacturer") "UNI-ROYAL(厚声)")
      )
      (libsource (lib "easyedapro") (part "0402WGF330JTCE"))
    )
    (comp (ref "R64")
      (value "33Ω")
      (footprint "easyedapro:R0402")
      (fields
        (field (name "Manufacturer Part") "0402WGF330JTCE")
        (field (name "Manufacturer") "UNI-ROYAL(厚声)")
      )
      (libsource (lib "easyedapro") (part "0402WGF330JTCE"))
    )
    (comp (ref "R65")
      (value "33Ω")
      (footprint "easyedapro:R0402")
      (fields
        (field (name "Manufacturer Part") "0402WGF330JTCE")
        (field (name "Manufacturer") "UNI-ROYAL(厚声)")
      )
      (libsource (lib "easyedapro") (part "0402WGF330JTCE"))
    )
    (comp (ref "R66")
      (value "33Ω")
      (footprint "easyedapro:R0402")
      (fields
        (field (name "Manufacturer Part") "0402WGF330JTCE")
        (field (name "Manufacturer") "UNI-ROYAL(厚声)")
      )
      (libsource (lib "easyedapro") (part "0402WGF330JTCE"))
    )
    (comp (ref "R67")
      (value "33Ω")
      (footprint "easyedapro:R0402")
      (fields
        (field (name "Manufacturer Part") "0402WGF330JTCE")
        (field (name "Manufacturer") "UNI-ROYAL(厚声)")
      )
      (libsource (lib "easyedapro") (part "0402WGF330JTCE"))
    )
    (comp (ref "R68")
      (value "33Ω")
      (footprint "easyedapro:R0402")
      (fields
        (field (name "Manufacturer Part") "0402WGF330JTCE")
        (field (name "Manufacturer") "UNI-ROYAL(厚声)")
      )
      (libsource (lib "easyedapro") (part "0402WGF330JTCE"))
    )
    (comp (ref "R69")
      (value "33Ω")
      (footprint "easyedapro:R0402")
      (fields
        (field (name "Manufacturer Part") "0402WGF330JTCE")
        (field (name "Manufacturer") "UNI-ROYAL(厚声)")
      )
      (libsource (lib "easyedapro") (part "0402WGF330JTCE"))
    )
    (comp (ref "R70")
      (value "33Ω")
      (footprint "easyedapro:R0402")
      (fields
        (field (name "Manufacturer Part") "0402WGF330JTCE")
        (field (name "Manufacturer") "UNI-ROYAL(厚声)")
      )
      (libsource (lib "easyedapro") (part "0402WGF330JTCE"))
    )
    (comp (ref "R71")
      (value "33Ω")
      (footprint "easyedapro:R0402")
      (fields
        (field (name "Manufacturer Part") "0402WGF330JTCE")
        (field (name "Manufacturer") "UNI-ROYAL(厚声)")
      )
      (libsource (lib "easyedapro") (part "0402WGF330JTCE"))
    )
    (comp (ref "R72")
      (value "33Ω")
      (footprint "easyedapro:R0402")
      (fields
        (field (name "Manufacturer Part") "0402WGF330JTCE")
        (field (name "Manufacturer") "UNI-ROYAL(厚声)")
      )
      (libsource (lib "easyedapro") (part "0402WGF330JTCE"))
    )
    (comp (ref "R73")
      (value "33Ω")
      (footprint "easyedapro:R0402")
      (fields
        (field (name "Manufacturer Part") "0402WGF330JTCE")
        (field (name "Manufacturer") "UNI-ROYAL(厚声)")
      )
      (libsource (lib "easyedapro") (part "0402WGF330JTCE"))
    )
    (comp (ref "R75")
      (value "33Ω")
      (footprint "easyedapro:R0402")
      (fields
        (field (name "Manufacturer Part") "0402WGF330JTCE")
        (field (name "Manufacturer") "UNI-ROYAL(厚声)")
      )
      (libsource (lib "easyedapro") (part "0402WGF330JTCE"))
    )
    (comp (ref "R76")
      (value "33Ω")
      (footprint "easyedapro:R0402")
      (fields
        (field (name "Manufacturer Part") "0402WGF330JTCE")
        (field (name "Manufacturer") "UNI-ROYAL(厚声)")
      )
      (libsource (lib "easyedapro") (part "0402WGF330JTCE"))
    )
    (comp (ref "R77")
      (value "33Ω")
      (footprint "easyedapro:R0402")
      (fields
        (field (name "Manufacturer Part") "0402WGF330JTCE")
        (field (name "Manufacturer") "UNI-ROYAL(厚声)")
      )
      (libsource (lib "easyedapro") (part "0402WGF330JTCE"))
    )
    (comp (ref "R78")
      (value "33Ω")
      (footprint "easyedapro:R0402")
      (fields
        (field (name "Manufacturer Part") "0402WGF330JTCE")
        (field (name "Manufacturer") "UNI-ROYAL(厚声)")
      )
      (libsource (lib "easyedapro") (part "0402WGF330JTCE"))
    )
    (comp (ref "R79")
      (value "33Ω")
      (footprint "easyedapro:R0402")
      (fields
        (field (name "Manufacturer Part") "0402WGF330JTCE")
        (field (name "Manufacturer") "UNI-ROYAL(厚声)")
      )
      (libsource (lib "easyedapro") (part "0402WGF330JTCE"))
    )
    (comp (ref "R80")
      (value "33Ω")
      (footprint "easyedapro:R0402")
      (fields
        (field (name "Manufacturer Part") "0402WGF330JTCE")
        (field (name "Manufacturer") "UNI-ROYAL(厚声)")
      )
      (libsource (lib "easyedapro") (part "0402WGF330JTCE"))
    )
    (comp (ref "R81")
      (value "33Ω")
      (footprint "easyedapro:R0402")
      (fields
        (field (name "Manufacturer Part") "0402WGF330JTCE")
        (field (name "Manufacturer") "UNI-ROYAL(厚声)")
      )
      (libsource (lib "easyedapro") (part "0402WGF330JTCE"))
    )
    (comp (ref "R82")
      (value "33Ω")
      (footprint "easyedapro:R0402")
      (fields
        (field (name "Manufacturer Part") "0402WGF330JTCE")
        (field (name "Manufacturer") "UNI-ROYAL(厚声)")
      )
      (libsource (lib "easyedapro") (part "0402WGF330JTCE"))
    )
    (comp (ref "R83")
      (value "33Ω")
      (footprint "easyedapro:R0402")
      (fields
        (field (name "Manufacturer Part") "0402WGF330JTCE")
        (field (name "Manufacturer") "UNI-ROYAL(厚声)")
      )
      (libsource (lib "easyedapro") (part "0402WGF330JTCE"))
    )
    (comp (ref "R84")
      (value "33Ω")
      (footprint "easyedapro:R0402")
      (fields
        (field (name "Manufacturer Part") "0402WGF330JTCE")
        (field (name "Manufacturer") "UNI-ROYAL(厚声)")
      )
      (libsource (lib "easyedapro") (part "0402WGF330JTCE"))
    )
    (comp (ref "R85")
      (value "33Ω")
      (footprint "easyedapro:R0402")
      (fields
        (field (name "Manufacturer Part") "0402WGF330JTCE")
        (field (name "Manufacturer") "UNI-ROYAL(厚声)")
      )
      (libsource (lib "easyedapro") (part "0402WGF330JTCE"))
    )
    (comp (ref "R86")
      (value "33Ω")
      (footprint "easyedapro:R0402")
      (fields
        (field (name "Manufacturer Part") "0402WGF330JTCE")
        (field (name "Manufacturer") "UNI-ROYAL(厚声)")
      )
      (libsource (lib "easyedapro") (part "0402WGF330JTCE"))
    )
    (comp (ref "R87")
      (value "33Ω")
      (footprint "easyedapro:R0402")
      (fields
        (field (name "Manufacturer Part") "0402WGF330JTCE")
        (field (name "Manufacturer") "UNI-ROYAL(厚声)")
      )
      (libsource (lib "easyedapro") (part "0402WGF330JTCE"))
    )
    (comp (ref "R88")
      (value "33Ω")
      (footprint "easyedapro:R0402")
      (fields
        (field (name "Manufacturer Part") "0402WGF330JTCE")
        (field (name "Manufacturer") "UNI-ROYAL(厚声)")
      )
      (libsource (lib "easyedapro") (part "0402WGF330JTCE"))
    )
    (comp (ref "R89")
      (value "1kΩ")
      (footprint "easyedapro:R1206")
      (fields
        (field (name "Manufacturer Part") "1206W4J0102T5E")
        (field (name "Manufacturer") "UNI-ROYAL(厚声)")
      )
      (libsource (lib "easyedapro") (part "1206W4J0102T5E"))
    )
    (comp (ref "SCREW1")
      (value "~")
      (footprint "easyedapro:Screw-Hole-M3")
      (libsource (lib "easyedapro") (part "Screw-Hole"))
    )
    (comp (ref "SCREW2")
      (value "~")
      (footprint "easyedapro:Screw-Hole-M3")
      (libsource (lib "easyedapro") (part "Screw-Hole"))
    )
    (comp (ref "SCREW3")
      (value "~")
      (footprint "easyedapro:Screw-Hole-M3")
      (libsource (lib "easyedapro") (part "Screw-Hole"))
    )
    (comp (ref "SCREW4")
      (value "~")
      (footprint "easyedapro:Screw-Hole-M3")
      (libsource (lib "easyedapro") (part "Screw-Hole"))
    )
    (comp (ref "U2")
      (value "ESP32-S3-WROOM-1-N16R2")
      (footprint "easyedapro:WIRELM-SMD_ESP32-S3-WROOM-1")
      (fields (field (name "Manufacturer") "ESPRESSIF(乐鑫)"))
      (libsource (lib "easyedapro") (part "ESP32-S3-WROOM-1(N16R2)"))
    )
    (comp (ref "U5")
      (value "W9825G6KH-6")
      (footprint "easyedapro:TSOP-54_L22.2-W10.2-P0.80-LS11.8-BL")
      (fields (field (name "Manufacturer") "Winbond(华邦)"))
      (libsource (lib "easyedapro") (part "W9825G6KH-6"))
    )
    (comp (ref "U6")
      (value "AP63200WU-7")
      (footprint "easyedapro:SOT-23-6_L2.9-W1.6-P0.95-LS2.8-BR")
      (fields (field (name "Manufacturer") "DIODES(美台)"))
      (libsource (lib "easyedapro") (part "AP63200WU-7"))
    )
    (comp (ref "U7")
      (value "AP63200WU-7")
      (footprint "easyedapro:SOT-23-6_L2.9-W1.6-P0.95-LS2.8-BR")
      (fields (field (name "Manufacturer") "DIODES(美台)"))
      (libsource (lib "easyedapro") (part "AP63200WU-7"))
    )
    (comp (ref "U8")
      (value "AMS1117-1.8")
      (footprint "easyedapro:SOT-223-4_L6.5-W3.5-P2.30-LS7.0-BR")
      (fields (field (name "Manufacturer") "AMS"))
      (libsource (lib "easyedapro") (part "AMS1117-1.8"))
    )
    (comp (ref "U9")
      (value "24MHz")
      (footprint "easyedapro:OSC-SMD_4P-L3.2-W2.5-BL")
      (fields (field (name "Manufacturer Part") "XOS32024000LT00351005") (field (name "Manufacturer") "同晶"))
      (libsource (lib "easyedapro") (part "XOS32024000LT00351005"))
    )
    (comp (ref "U10")
      (value "TPS645-5NC60")
      (footprint "easyedapro:SW-SMD_4P-L6.0-W6.0-P4.50-LS9.2")
      (fields (field (name "Manufacturer") "ROCPU Switches(台普)"))
      (libsource (lib "easyedapro") (part "TPS645-5NC60"))
    )
    (comp (ref "U11")
      (value "AP63200WU-7")
      (footprint "easyedapro:SOT-23-6_L2.9-W1.6-P0.95-LS2.8-BR")
      (fields (field (name "Manufacturer") "DIODES(美台)"))
      (libsource (lib "easyedapro") (part "AP63200WU-7"))
    )
    (comp (ref "U12")
      (value "AP63200WU-7")
      (footprint "easyedapro:SOT-23-6_L2.9-W1.6-P0.95-LS2.8-BR")
      (fields (field (name "Manufacturer") "DIODES(美台)"))
      (libsource (lib "easyedapro") (part "AP63200WU-7"))
    )
    (comp (ref "USB1")
      (value "TYPE-C16PIN")
      (footprint "easyedapro:USB-C-SMD_TYPE-C16PIN")
      (fields (field (name "Manufacturer") "SHOU HAN(首韩)"))
      (libsource (lib "easyedapro") (part "TYPE-C16PIN"))
    )
    (comp (ref "USB2")
      (value "TYPE-C16PIN")
      (footprint "easyedapro:USB-C-SMD_TYPE-C16PIN")
      (fields (field (name "Manufacturer") "SHOU HAN(首韩)"))
      (libsource (lib "easyedapro") (part "TYPE-C16PIN"))
    )
    (comp (ref "C37")
      (value "100nF")
      (footprint "easyedapro:C01005")
      (description "Capacitance:100nF Tolerance:±10% Tolerance:±10% Voltage Rating:6.3V Temperature Coefficient:X5R")
      (fields
        (field (name "Manufacturer Part") "GRM022R60J104KE15D")
        (field (name "Manufacturer") "muRata(村田)")
      )
      (libsource (lib "easyedapro") (part "GRM022R60J104KE15D"))
    )
    (comp (ref "C39")
      (value "100nF")
      (footprint "easyedapro:C01005")
      (description "Capacitance:100nF Tolerance:±10% Tolerance:±10% Voltage Rating:6.3V Temperature Coefficient:X5R")
      (fields
        (field (name "Manufacturer Part") "GRM022R60J104KE15D")
        (field (name "Manufacturer") "muRata(村田)")
      )
      (libsource (lib "easyedapro") (part "GRM022R60J104KE15D"))
    )
    (comp (ref "C40")
      (value "100nF")
      (footprint "easyedapro:C01005")
      (description "Capacitance:100nF Tolerance:±10% Tolerance:±10% Voltage Rating:6.3V Temperature Coefficient:X5R")
      (fields
        (field (name "Manufacturer Part") "GRM022R60J104KE15D")
        (field (name "Manufacturer") "muRata(村田)")
      )
      (libsource (lib "easyedapro") (part "GRM022R60J104KE15D"))
    )
    (comp (ref "C41")
      (value "100nF")
      (footprint "easyedapro:C01005")
      (description "Capacitance:100nF Tolerance:±10% Tolerance:±10% Voltage Rating:6.3V Temperature Coefficient:X5R")
      (fields
        (field (name "Manufacturer Part") "GRM022R60J104KE15D")
        (field (name "Manufacturer") "muRata(村田)")
      )
      (libsource (lib "easyedapro") (part "GRM022R60J104KE15D"))
    )
    (comp (ref "C42")
      (value "100nF")
      (footprint "easyedapro:C01005")
      (description "Capacitance:100nF Tolerance:±10% Tolerance:±10% Voltage Rating:6.3V Temperature Coefficient:X5R")
      (fields
        (field (name "Manufacturer Part") "GRM022R60J104KE15D")
        (field (name "Manufacturer") "muRata(村田)")
      )
      (libsource (lib "easyedapro") (part "GRM022R60J104KE15D"))
    )
    (comp (ref "C43")
      (value "100nF")
      (footprint "easyedapro:C01005")
      (description "Capacitance:100nF Tolerance:±10% Tolerance:±10% Voltage Rating:6.3V Temperature Coefficient:X5R")
      (fields
        (field (name "Manufacturer Part") "GRM022R60J104KE15D")
        (field (name "Manufacturer") "muRata(村田)")
      )
      (libsource (lib "easyedapro") (part "GRM022R60J104KE15D"))
    )
    (comp (ref "C44")
      (value "100nF")
      (footprint "easyedapro:C01005")
      (description "Capacitance:100nF Tolerance:±10% Tolerance:±10% Voltage Rating:6.3V Temperature Coefficient:X5R")
      (fields
        (field (name "Manufacturer Part") "GRM022R60J104KE15D")
        (field (name "Manufacturer") "muRata(村田)")
      )
      (libsource (lib "easyedapro") (part "GRM022R60J104KE15D"))
    )
    (comp (ref "C45")
      (value "100nF")
      (footprint "easyedapro:C01005")
      (description "Capacitance:100nF Tolerance:±10% Tolerance:±10% Voltage Rating:6.3V Temperature Coefficient:X5R")
      (fields
        (field (name "Manufacturer Part") "GRM022R60J104KE15D")
        (field (name "Manufacturer") "muRata(村田)")
      )
      (libsource (lib "easyedapro") (part "GRM022R60J104KE15D"))
    )
    (comp (ref "C46")
      (value "100nF")
      (footprint "easyedapro:C01005")
      (description "Capacitance:100nF Tolerance:±10% Tolerance:±10% Voltage Rating:6.3V Temperature Coefficient:X5R")
      (fields
        (field (name "Manufacturer Part") "GRM022R60J104KE15D")
        (field (name "Manufacturer") "muRata(村田)")
      )
      (libsource (lib "easyedapro") (part "GRM022R60J104KE15D"))
    )
    (comp (ref "C47")
      (value "100nF")
      (footprint "easyedapro:C01005")
      (description "Capacitance:100nF Tolerance:±10% Tolerance:±10% Voltage Rating:6.3V Temperature Coefficient:X5R")
      (fields
        (field (name "Manufacturer Part") "GRM022R60J104KE15D")
        (field (name "Manufacturer") "muRata(村田)")
      )
      (libsource (lib "easyedapro") (part "GRM022R60J104KE15D"))
    )
    (comp (ref "C48")
      (value "100nF")
      (footprint "easyedapro:C01005")
      (description "Capacitance:100nF Tolerance:±10% Tolerance:±10% Voltage Rating:6.3V Temperature Coefficient:X5R")
      (fields
        (field (name "Manufacturer Part") "GRM022R60J104KE15D")
        (field (name "Manufacturer") "muRata(村田)")
      )
      (libsource (lib "easyedapro") (part "GRM022R60J104KE15D"))
    )
    (comp (ref "C49")
      (value "100nF")
      (footprint "easyedapro:C01005")
      (description "Capacitance:100nF Tolerance:±10% Tolerance:±10% Voltage Rating:6.3V Temperature Coefficient:X5R")
      (fields
        (field (name "Manufacturer Part") "GRM022R60J104KE15D")
        (field (name "Manufacturer") "muRata(村田)")
      )
      (libsource (lib "easyedapro") (part "GRM022R60J104KE15D"))
    )
    (comp (ref "C50")
      (value "100nF")
      (footprint "easyedapro:C01005")
      (description "Capacitance:100nF Tolerance:±10% Tolerance:±10% Voltage Rating:6.3V Temperature Coefficient:X5R")
      (fields
        (field (name "Manufacturer Part") "GRM022R60J104KE15D")
        (field (name "Manufacturer") "muRata(村田)")
      )
      (libsource (lib "easyedapro") (part "GRM022R60J104KE15D"))
    )
    (comp (ref "C51")
      (value "100nF")
      (footprint "easyedapro:C01005")
      (description "Capacitance:100nF Tolerance:±10% Tolerance:±10% Voltage Rating:6.3V Temperature Coefficient:X5R")
      (fields
        (field (name "Manufacturer Part") "GRM022R60J104KE15D")
        (field (name "Manufacturer") "muRata(村田)")
      )
      (libsource (lib "easyedapro") (part "GRM022R60J104KE15D"))
    )
    (comp (ref "C52")
      (value "100nF")
      (footprint "easyedapro:C01005")
      (description "Capacitance:100nF Tolerance:±10% Tolerance:±10% Voltage Rating:6.3V Temperature Coefficient:X5R")
      (fields
        (field (name "Manufacturer Part") "GRM022R60J104KE15D")
        (field (name "Manufacturer") "muRata(村田)")
      )
      (libsource (lib "easyedapro") (part "GRM022R60J104KE15D"))
    )
    (comp (ref "C53")
      (value "100nF")
      (footprint "easyedapro:C01005")
      (description "Capacitance:100nF Tolerance:±10% Tolerance:±10% Voltage Rating:6.3V Temperature Coefficient:X5R")
      (fields
        (field (name "Manufacturer Part") "GRM022R60J104KE15D")
        (field (name "Manufacturer") "muRata(村田)")
      )
      (libsource (lib "easyedapro") (part "GRM022R60J104KE15D"))
    )
    (comp (ref "C54")
      (value "100nF")
      (footprint "easyedapro:C01005")
      (description "Capacitance:100nF Tolerance:±10% Tolerance:±10% Voltage Rating:6.3V Temperature Coefficient:X5R")
      (fields
        (field (name "Manufacturer Part") "GRM022R60J104KE15D")
        (field (name "Manufacturer") "muRata(村田)")
      )
      (libsource (lib "easyedapro") (part "GRM022R60J104KE15D"))
    )
    (comp (ref "C55")
      (value "100nF")
      (footprint "easyedapro:C01005")
      (description "Capacitance:100nF Tolerance:±10% Tolerance:±10% Voltage Rating:6.3V Temperature Coefficient:X5R")
      (fields
        (field (name "Manufacturer Part") "GRM022R60J104KE15D")
        (field (name "Manufacturer") "muRata(村田)")
      )
      (libsource (lib "easyedapro") (part "GRM022R60J104KE15D"))
    )
    (comp (ref "C56")
      (value "100nF")
      (footprint "easyedapro:C01005")
      (description "Capacitance:100nF Tolerance:±10% Tolerance:±10% Voltage Rating:6.3V Temperature Coefficient:X5R")
      (fields
        (field (name "Manufacturer Part") "GRM022R60J104KE15D")
        (field (name "Manufacturer") "muRata(村田)")
      )
      (libsource (lib "easyedapro") (part "GRM022R60J104KE15D"))
    )
    (comp (ref "C57")
      (value "100nF")
      (footprint "easyedapro:C01005")
      (description "Capacitance:100nF Tolerance:±10% Tolerance:±10% Voltage Rating:6.3V Temperature Coefficient:X5R")
      (fields
        (field (name "Manufacturer Part") "GRM022R60J104KE15D")
        (field (name "Manufacturer") "muRata(村田)")
      )
      (libsource (lib "easyedapro") (part "GRM022R60J104KE15D"))
    )
    (comp (ref "C58")
      (value "22uF")
      (footprint "easyedapro:C0603")
      (description "Capacitance:22uF Tolerance:±20% Tolerance:±20% Voltage Rating:6.3V Temperature Coefficient:X5R")
      (fields
        (field (name "Manufacturer Part") "TCC0603X5R226M6R3CT")
        (field (name "Manufacturer") "CCTC(三环)")
      )
      (libsource (lib "easyedapro") (part "TCC0603X5R226M6R3CT"))
    )
    (comp (ref "C59")
      (value "22uF")
      (footprint "easyedapro:C0603")
      (description "Capacitance:22uF Tolerance:±20% Tolerance:±20% Voltage Rating:6.3V Temperature Coefficient:X5R")
      (fields
        (field (name "Manufacturer Part") "TCC0603X5R226M6R3CT")
        (field (name "Manufacturer") "CCTC(三环)")
      )
      (libsource (lib "easyedapro") (part "TCC0603X5R226M6R3CT"))
    )
    (comp (ref "C61")
      (value "22uF")
      (footprint "easyedapro:C0603")
      (description "Capacitance:22uF Tolerance:±20% Tolerance:±20% Voltage Rating:6.3V Temperature Coefficient:X5R")
      (fields
        (field (name "Manufacturer Part") "TCC0603X5R226M6R3CT")
        (field (name "Manufacturer") "CCTC(三环)")
      )
      (libsource (lib "easyedapro") (part "TCC0603X5R226M6R3CT"))
    )
    (comp (ref "C62")
      (value "100nF")
      (footprint "easyedapro:C01005")
      (description "Capacitance:100nF Tolerance:±10% Tolerance:±10% Voltage Rating:6.3V Temperature Coefficient:X5R")
      (fields
        (field (name "Manufacturer Part") "GRM022R60J104KE15D")
        (field (name "Manufacturer") "muRata(村田)")
      )
      (libsource (lib "easyedapro") (part "GRM022R60J104KE15D"))
    )
    (comp (ref "C63")
      (value "100nF")
      (footprint "easyedapro:C01005")
      (description "Capacitance:100nF Tolerance:±10% Tolerance:±10% Voltage Rating:6.3V Temperature Coefficient:X5R")
      (fields
        (field (name "Manufacturer Part") "GRM022R60J104KE15D")
        (field (name "Manufacturer") "muRata(村田)")
      )
      (libsource (lib "easyedapro") (part "GRM022R60J104KE15D"))
    )
    (comp (ref "R23")
      (value "10kΩ")
      (footprint "easyedapro:R0402")
      (fields
        (field (name "Manufacturer Part") "0402WGF1002TCE")
        (field (name "Manufacturer") "UNI-ROYAL(厚声)")
      )
      (libsource (lib "easyedapro") (part "0402WGF1002TCE"))
    )
    (comp (ref "R24")
      (value "10kΩ")
      (footprint "easyedapro:R0402")
      (fields
        (field (name "Manufacturer Part") "0402WGF1002TCE")
        (field (name "Manufacturer") "UNI-ROYAL(厚声)")
      )
      (libsource (lib "easyedapro") (part "0402WGF1002TCE"))
    )
    (comp (ref "R25")
      (value "10kΩ")
      (footprint "easyedapro:R0402")
      (fields
        (field (name "Manufacturer Part") "0402WGF1002TCE")
        (field (name "Manufacturer") "UNI-ROYAL(厚声)")
      )
      (libsource (lib "easyedapro") (part "0402WGF1002TCE"))
    )
    (comp (ref "TP1")
      (value "~")
      (footprint "easyedapro:Test-Point-0.5mm")
      (description "Test-Point")
      (libsource (lib "easyedapro") (part "Test-Point"))
    )
    (comp (ref "TP2")
      (value "~")
      (footprint "easyedapro:Test-Point-0.5mm")
      (description "Test-Point")
      (libsource (lib "easyedapro") (part "Test-Point"))
    )
    (comp (ref "TP3")
      (value "~")
      (footprint "easyedapro:Test-Point-0.5mm")
      (description "Test-Point")
      (libsource (lib "easyedapro") (part "Test-Point"))
    )
    (comp (ref "TP4")
      (value "~")
      (footprint "easyedapro:Test-Point-0.5mm")
      (description "Test-Point")
      (libsource (lib "easyedapro") (part "Test-Point"))
    )
    (comp (ref "TP6")
      (value "~")
      (footprint "easyedapro:Test-Point-0.5mm")
      (description "Test-Point")
      (libsource (lib "easyedapro") (part "Test-Point"))
    )
    (comp (ref "U1")
      (value "LFE5U-25F-6BG256C")
      (footprint "easyedapro:CABGA-256_L14.0-W14.0-R16-C16-P0.80-TL")
      (fields (field (name "Manufacturer") "LATTICE(莱迪思)"))
      (libsource (lib "easyedapro") (part "LFE5U-25F-6BG256C"))
    )
  )
  (nets
    (net (code "1") (name "+1V1") (class "Default")
      (node (ref "C25") (pin "2") (pinfunction "2_2") (pintype "unspecified"))
      (node (ref "C27") (pin "2") (pinfunction "2_2") (pintype "unspecified"))
      (node (ref "C28") (pin "2") (pinfunction "2_2") (pintype "unspecified"))
      (node (ref "C41") (pin "1") (pinfunction "1_1") (pintype "unspecified"))
      (node (ref "C42") (pin "1") (pinfunction "1_1") (pintype "unspecified"))
      (node (ref "C43") (pin "1") (pinfunction "1_1") (pintype "unspecified"))
      (node (ref "C44") (pin "1") (pinfunction "1_1") (pintype "unspecified"))
      (node (ref "C49") (pin "1") (pinfunction "1_1") (pintype "unspecified"))
      (node (ref "C53") (pin "1") (pinfunction "1_1") (pintype "unspecified"))
      (node (ref "C54") (pin "1") (pinfunction "1_1") (pintype "unspecified"))
      (node (ref "C61") (pin "1") (pinfunction "1_1") (pintype "unspecified"))
      (node (ref "L2") (pin "2") (pinfunction "2_2") (pintype "unspecified"))
      (node (ref "R15") (pin "2") (pinfunction "2_2") (pintype "input"))
      (node (ref "U1") (pin "G6") (pinfunction "VCC_G6") (pintype "unspecified"))
      (node (ref "U1") (pin "G7") (pinfunction "VCC_G7") (pintype "unspecified"))
      (node (ref "U1") (pin "L10") (pinfunction "VCC_L10") (pintype "unspecified"))
      (node (ref "U1") (pin "L8") (pinfunction "VCC_L8") (pintype "unspecified"))
      (node (ref "U1") (pin "L9") (pinfunction "VCC_L9") (pintype "unspecified"))
    )
    (net (code "2") (name "+1V8") (class "Default")
      (node (ref "C29") (pin "1") (pinfunction "1_1") (pintype "unspecified"))
      (node (ref "C32") (pin "2") (pinfunction "2_2") (pintype "input"))
      (node (ref "C35") (pin "1") (pinfunction "1_1") (pintype "unspecified"))
      (node (ref "C62") (pin "1") (pinfunction "1_1") (pintype "unspecified"))
      (node (ref "C63") (pin "1") (pinfunction "1_1") (pintype "unspecified"))
      (node (ref "P1") (pin "11") (pinfunction "11_11") (pintype "input"))
      (node (ref "R38") (pin "2") (pinfunction "2_2") (pintype "input"))
      (node (ref "R39") (pin "2") (pinfunction "2_2") (pintype "input"))
      (node (ref "U1") (pin "F10") (pinfunction "VCCIO1_F10") (pintype "unspecified"))
      (node (ref "U1") (pin "F11") (pinfunction "VCCIO1_F11") (pintype "unspecified"))
      (node (ref "U8") (pin "2") (pinfunction "Out_2") (pintype "unspecified"))
    )
    (net (code "3") (name "+2V5") (class "Default")
      (node (ref "C65") (pin "2") (pinfunction "2_2") (pintype "unspecified"))
      (node (ref "C67") (pin "2") (pinfunction "2_2") (pintype "unspecified"))
      (node (ref "C68") (pin "2") (pinfunction "2_2") (pintype "unspecified"))
      (node (ref "L3") (pin "2") (pinfunction "2_2") (pintype "unspecified"))
      (node (ref "R41") (pin "2") (pinfunction "2_2") (pintype "unspecified"))
      (node (ref "U1") (pin "G11") (pinfunction "VCCAUX_G11") (pintype "unspecified"))
      (node (ref "U1") (pin "L7") (pinfunction "VCCAUX_L7") (pintype "unspecified"))
    )
    (net (code "4") (name "+2V8") (class "Default")
      (node (ref "C34") (pin "1") (pinfunction "1_1") (pintype "unspecified"))
      (node (ref "C70") (pin "2") (pinfunction "2_2") (pintype "unspecified"))
      (node (ref "C72") (pin "2") (pinfunction "2_2") (pintype "unspecified"))
      (node (ref "C73") (pin "2") (pinfunction "2_2") (pintype "unspecified"))
      (node (ref "C74") (pin "1") (pinfunction "1_1") (pintype "unspecified"))
      (node (ref "L4") (pin "2") (pinfunction "2_2") (pintype "unspecified"))
      (node (ref "P1") (pin "24") (pinfunction "24_24") (pintype "input"))
      (node (ref "P1") (pin "4") (pinfunction "4_4") (pintype "input"))
      (node (ref "R47") (pin "2") (pinfunction "2_2") (pintype "input"))
    )
    (net (code "5") (name "+3V3") (class "Default")
      (node (ref "C10") (pin "1") (pinfunction "1_1") (pintype "unspecified"))
      (node (ref "C11") (pin "1") (pinfunction "1_1") (pintype "unspecified"))
      (node (ref "C12") (pin "1") (pinfunction "1_1") (pintype "unspecified"))
      (node (ref "C13") (pin "1") (pinfunction "1_1") (pintype "unspecified"))
      (node (ref "C14") (pin "1") (pinfunction "1_1") (pintype "unspecified"))
      (node (ref "C15") (pin "2") (pinfunction "2_2") (pintype "unspecified"))
      (node (ref "C16") (pin "2") (pinfunction "2_2") (pintype "unspecified"))
      (node (ref "C17") (pin "2") (pinfunction "2_2") (pintype "unspecified"))
      (node (ref "C19") (pin "2") (pinfunction "2_2") (pintype "unspecified"))
      (node (ref "C22") (pin "2") (pinfunction "2_2") (pintype "unspecified"))
      (node (ref "C23") (pin "2") (pinfunction "2_2") (pintype "unspecified"))
      (node (ref "C37") (pin "1") (pinfunction "1_1") (pintype "unspecified"))
      (node (ref "C39") (pin "1") (pinfunction "1_1") (pintype "unspecified"))
      (node (ref "C40") (pin "1") (pinfunction "1_1") (pintype "unspecified"))
      (node (ref "C45") (pin "1") (pinfunction "1_1") (pintype "unspecified"))
      (node (ref "C46") (pin "1") (pinfunction "1_1") (pintype "unspecified"))
      (node (ref "C47") (pin "1") (pinfunction "1_1") (pintype "unspecified"))
      (node (ref "C48") (pin "1") (pinfunction "1_1") (pintype "unspecified"))
      (node (ref "C50") (pin "1") (pinfunction "1_1") (pintype "unspecified"))
      (node (ref "C51") (pin "1") (pinfunction "1_1") (pintype "unspecified"))
      (node (ref "C52") (pin "1") (pinfunction "1_1") (pintype "unspecified"))
      (node (ref "C55") (pin "1") (pinfunction "1_1") (pintype "unspecified"))
      (node (ref "C56") (pin "1") (pinfunction "1_1") (pintype "unspecified"))
      (node (ref "C57") (pin "1") (pinfunction "1_1") (pintype "unspecified"))
      (node (ref "C58") (pin "1") (pinfunction "1_1") (pintype "unspecified"))
      (node (ref "C59") (pin "1") (pinfunction "1_1") (pintype "unspecified"))
      (node (ref "C8") (pin "1") (pinfunction "1_1") (pintype "input"))
      (node (ref "CARD1") (pin "4") (pinfunction "VDD_4") (pintype "input"))
      (node (ref "H1") (pin "5") (pinfunction "5_5") (pintype "input"))
      (node (ref "L1") (pin "2") (pinfunction "2_2") (pintype "unspecified"))
      (node (ref "R1") (pin "2") (pinfunction "2_2") (pintype "input"))
      (node (ref "R11") (pin "2") (pinfunction "2_2") (pintype "unspecified"))
      (node (ref "R16") (pin "2") (pinfunction "2_2") (pintype "unspecified"))
      (node (ref "R17") (pin "2") (pinfunction "2_2") (pintype "unspecified"))
      (node (ref "R18") (pin "2") (pinfunction "2_2") (pintype "unspecified"))
      (node (ref "R19") (pin "2") (pinfunction "2_2") (pintype "unspecified"))
      (node (ref "R20") (pin "2") (pinfunction "2_2") (pintype "unspecified"))
      (node (ref "R21") (pin "2") (pinfunction "2_2") (pintype "input"))
      (node (ref "R22") (pin "2") (pinfunction "2_2") (pintype "input"))
      (node (ref "R23") (pin "1") (pinfunction "1_1") (pintype "input"))
      (node (ref "R3") (pin "1") (pinfunction "1_1") (pintype "input"))
      (node (ref "R4") (pin "1") (pinfunction "1_1") (pintype "input"))
      (node (ref "R5") (pin "2") (pinfunction "2_2") (pintype "input"))
      (node (ref "R7") (pin "2") (pinfunction "2_2") (pintype "input"))
      (node (ref "R89") (pin "1") (pinfunction "1_1") (pintype "input"))
      (node (ref "U1") (pin "F6") (pinfunction "VCCIO0_F6") (pintype "unspecified"))
      (node (ref "U1") (pin "F7") (pinfunction "VCCIO0_F7") (pintype "unspecified"))
      (node (ref "U1") (pin "G9") (pinfunction "VCC_G9") (pintype "unspecified"))
      (node (ref "U1") (pin "H11") (pinfunction "VCCIO2_H11") (pintype "unspecified"))
      (node (ref "U1") (pin "H6") (pinfunction "VCCIO7_H6") (pintype "unspecified"))
      (node (ref "U1") (pin "H7") (pinfunction "VCCIO7_H7") (pintype "unspecified"))
      (node (ref "U1") (pin "J11") (pinfunction "VCCIO2_J11") (pintype "unspecified"))
      (node (ref "U1") (pin "J6") (pinfunction "VCCIO6_J6") (pintype "unspecified"))
      (node (ref "U1") (pin "J7") (pinfunction "VCCIO6_J7") (pintype "unspecified"))
      (node (ref "U1") (pin "K11") (pinfunction "VCCIO3_K11") (pintype "unspecified"))
      (node (ref "U1") (pin "L11") (pinfunction "VCCIO3_L11") (pintype "unspecified"))
      (node (ref "U1") (pin "L6") (pinfunction "VCCIO8_L6") (pintype "unspecified"))
      (node (ref "U2") (pin "2") (pinfunction "3V3_2") (pintype "unspecified"))
      (node (ref "U5") (pin "1") (pinfunction "VDD_1") (pintype "unspecified"))
      (node (ref "U5") (pin "14") (pinfunction "VDD_14") (pintype "unspecified"))
      (node (ref "U5") (pin "27") (pinfunction "VDD_27") (pintype "unspecified"))
      (node (ref "U5") (pin "3") (pinfunction "VDDQ_3") (pintype "unspecified"))
      (node (ref "U5") (pin "43") (pinfunction "VDDQ_43") (pintype "unspecified"))
      (node (ref "U5") (pin "49") (pinfunction "VDDQ_49") (pintype "unspecified"))
      (node (ref "U5") (pin "9") (pinfunction "VDDQ_9") (pintype "unspecified"))
      (node (ref "U9") (pin "1") (pinfunction "OE/NC_1") (pintype "unspecified"))
      (node (ref "U9") (pin "4") (pinfunction "VDD_4") (pintype "unspecified"))
    )
    (net (code "6") (name "+5V") (class "Default")
      (node (ref "C20") (pin "2") (pinfunction "2_2") (pintype "unspecified"))
      (node (ref "C26") (pin "2") (pinfunction "2_2") (pintype "unspecified"))
      (node (ref "C30") (pin "1") (pinfunction "1_1") (pintype "unspecified"))
      (node (ref "C31") (pin "2") (pinfunction "2_2") (pintype "input"))
      (node (ref "C33") (pin "2") (pinfunction "2_2") (pintype "input"))
      (node (ref "C66") (pin "2") (pinfunction "2_2") (pintype "unspecified"))
      (node (ref "C71") (pin "2") (pinfunction "2_2") (pintype "unspecified"))
      (node (ref "C75") (pin "2") (pinfunction "2_2") (pintype "input"))
      (node (ref "C76") (pin "1") (pinfunction "1_1") (pintype "unspecified"))
      (node (ref "U11") (pin "2") (pinfunction "EN_2") (pintype "unspecified"))
      (node (ref "U11") (pin "3") (pinfunction "VIN_3") (pintype "unspecified"))
      (node (ref "U12") (pin "2") (pinfunction "EN_2") (pintype "unspecified"))
      (node (ref "U12") (pin "3") (pinfunction "VIN_3") (pintype "unspecified"))
      (node (ref "U6") (pin "2") (pinfunction "EN_2") (pintype "unspecified"))
      (node (ref "U6") (pin "3") (pinfunction "VIN_3") (pintype "unspecified"))
      (node (ref "U7") (pin "2") (pinfunction "EN_2") (pintype "unspecified"))
      (node (ref "U7") (pin "3") (pinfunction "VIN_3") (pintype "unspecified"))
      (node (ref "U8") (pin "3") (pinfunction "In_3") (pintype "unspecified"))
      (node (ref "USB1") (pin "A4B9") (pinfunction "VBUS_A4B9") (pintype "unspecified"))
      (node (ref "USB1") (pin "B4A9") (pinfunction "VBUS_B4A9") (pintype "unspecified"))
    )
    (net (code "7") (name "CCLK") (class "Default")
      (node (ref "R6") (pin "1") (pinfunction "1_1") (pintype "input"))
      (node (ref "U1") (pin "N9") (pinfunction "CCLK_N9") (pintype "unspecified"))
    )
    (net (code "8") (name "CRYSTAL") (class "Default")
      (node (ref "U1") (pin "M1") (pinfunction "PL26C_M1") (pintype "unspecified"))
      (node (ref "U9") (pin "3") (pinfunction "OUT_3") (pintype "unspecified"))
    )
    (net (code "9") (name "D0") (class "Default")
      (node (ref "R26") (pin "1") (pinfunction "1_1") (pintype "input"))
      (node (ref "U1") (pin "E2") (pinfunction "PL8B_E2") (pintype "unspecified"))
    )
    (net (code "10") (name "D1") (class "Default")
      (node (ref "R27") (pin "1") (pinfunction "1_1") (pintype "input"))
      (node (ref "U1") (pin "E1") (pinfunction "PL11D_E1") (pintype "unspecified"))
    )
    (net (code "11") (name "D2") (class "Default")
      (node (ref "R28") (pin "1") (pinfunction "1_1") (pintype "input"))
      (node (ref "U1") (pin "F2") (pinfunction "PL11C_F2") (pintype "unspecified"))
    )
    (net (code "12") (name "D3") (class "Default")
      (node (ref "R29") (pin "1") (pinfunction "1_1") (pintype "input"))
      (node (ref "U1") (pin "F1") (pinfunction "PL14A_F1") (pintype "unspecified"))
    )
    (net (code "13") (name "D4") (class "Default")
      (node (ref "R30") (pin "1") (pinfunction "1_1") (pintype "input"))
      (node (ref "U1") (pin "G2") (pinfunction "PL14B_G2") (pintype "unspecified"))
    )
    (net (code "14") (name "D5") (class "Default")
      (node (ref "R31") (pin "1") (pinfunction "1_1") (pintype "input"))
      (node (ref "U1") (pin "G1") (pinfunction "PL20A_G1") (pintype "unspecified"))
    )
    (net (code "15") (name "D6") (class "Default")
      (node (ref "R32") (pin "1") (pinfunction "1_1") (pintype "input"))
      (node (ref "U1") (pin "J1") (pinfunction "PL23A_J1") (pintype "unspecified"))
    )
    (net (code "16") (name "D7") (class "Default")
      (node (ref "R34") (pin "1") (pinfunction "1_1") (pintype "input"))
      (node (ref "U1") (pin "J2") (pinfunction "PL23B_J2") (pintype "unspecified"))
    )
    (net (code "17") (name "DIN") (class "Default")
      (node (ref "R87") (pin "1") (pinfunction "1_1") (pintype "input"))
      (node (ref "U1") (pin "T8") (pinfunction "PB11B_T8") (pintype "unspecified"))
    )
    (net (code "18") (name "DN") (class "Default")
      (node (ref "U2") (pin "13") (pinfunction "IO19_13") (pintype "unspecified"))
      (node (ref "USB2") (pin "A7") (pinfunction "DN1_A7") (pintype "unspecified"))
    )
    (net (code "19") (name "DONE") (class "Default")
      (node (ref "R3") (pin "2") (pinfunction "2_2") (pintype "input"))
      (node (ref "U1") (pin "P9") (pinfunction "DONE_P9") (pintype "unspecified"))
      (node (ref "U2") (pin "22") (pinfunction "IO14_22") (pintype "unspecified"))
    )
    (net (code "20") (name "DOUT") (class "Default")
      (node (ref "R88") (pin "1") (pinfunction "1_1") (pintype "input"))
      (node (ref "U1") (pin "M8") (pinfunction "PB15B_M8") (pintype "unspecified"))
    )
    (net (code "21") (name "DP") (class "Default")
      (node (ref "U2") (pin "14") (pinfunction "IO20_14") (pintype "unspecified"))
      (node (ref "USB2") (pin "A6") (pinfunction "DP1_A6") (pintype "unspecified"))
    )
    (net (code "22") (name "FSCL") (class "Default")
      (node (ref "R72") (pin "1") (pinfunction "1_1") (pintype "input"))
      (node (ref "U1") (pin "A10") (pinfunction "PT42B_A10") (pintype "unspecified"))
    )
    (net (code "23") (name "FSDA") (class "Default")
      (node (ref "R71") (pin "1") (pinfunction "1_1") (pintype "input"))
      (node (ref "U1") (pin "B9") (pinfunction "PT38A_B9") (pintype "unspecified"))
    )
    (net (code "24") (name "GND") (class "Default")
      (node (ref "C10") (pin "2") (pinfunction "2_2") (pintype "unspecified"))
      (node (ref "C11") (pin "2") (pinfunction "2_2") (pintype "unspecified"))
      (node (ref "C12") (pin "2") (pinfunction "2_2") (pintype "unspecified"))
      (node (ref "C13") (pin "2") (pinfunction "2_2") (pintype "unspecified"))
      (node (ref "C14") (pin "2") (pinfunction "2_2") (pintype "unspecified"))
      (node (ref "C15") (pin "1") (pinfunction "1_1") (pintype "unspecified"))
      (node (ref "C16") (pin "1") (pinfunction "1_1") (pintype "unspecified"))
      (node (ref "C17") (pin "1") (pinfunction "1_1") (pintype "unspecified"))
      (node (ref "C20") (pin "1") (pinfunction "1_1") (pintype "unspecified"))
      (node (ref "C22") (pin "1") (pinfunction "1_1") (pintype "unspecified"))
      (node (ref "C23") (pin "1") (pinfunction "1_1") (pintype "unspecified"))
      (node (ref "C26") (pin "1") (pinfunction "1_1") (pintype "unspecified"))
      (node (ref "C27") (pin "1") (pinfunction "1_1") (pintype "unspecified"))
      (node (ref "C28") (pin "1") (pinfunction "1_1") (pintype "unspecified"))
      (node (ref "C33") (pin "1") (pinfunction "1_1") (pintype "input"))
      (node (ref "C34") (pin "2") (pinfunction "2_2") (pintype "unspecified"))
      (node (ref "C35") (pin "2") (pinfunction "2_2") (pintype "unspecified"))
      (node (ref "C37") (pin "2") (pinfunction "2_2") (pintype "unspecified"))
      (node (ref "C39") (pin "2") (pinfunction "2_2") (pintype "unspecified"))
      (node (ref "C40") (pin "2") (pinfunction "2_2") (pintype "unspecified"))
      (node (ref "C41") (pin "2") (pinfunction "2_2") (pintype "unspecified"))
      (node (ref "C42") (pin "2") (pinfunction "2_2") (pintype "unspecified"))
      (node (ref "C43") (pin "2") (pinfunction "2_2") (pintype "unspecified"))
      (node (ref "C44") (pin "2") (pinfunction "2_2") (pintype "unspecified"))
      (node (ref "C45") (pin "2") (pinfunction "2_2") (pintype "unspecified"))
      (node (ref "C46") (pin "2") (pinfunction "2_2") (pintype "unspecified"))
      (node (ref "C47") (pin "2") (pinfunction "2_2") (pintype "unspecified"))
      (node (ref "C48") (pin "2") (pinfunction "2_2") (pintype "unspecified"))
      (node (ref "C49") (pin "2") (pinfunction "2_2") (pintype "unspecified"))
      (node (ref "C50") (pin "2") (pinfunction "2_2") (pintype "unspecified"))
      (node (ref "C51") (pin "2") (pinfunction "2_2") (pintype "unspecified"))
      (node (ref "C52") (pin "2") (pinfunction "2_2") (pintype "unspecified"))
      (node (ref "C53") (pin "2") (pinfunction "2_2") (pintype "unspecified"))
      (node (ref "C54") (pin "2") (pinfunction "2_2") (pintype "unspecified"))
      (node (ref "C55") (pin "2") (pinfunction "2_2") (pintype "unspecified"))
      (node (ref "C56") (pin "2") (pinfunction "2_2") (pintype "unspecified"))
      (node (ref "C57") (pin "2") (pinfunction "2_2") (pintype "unspecified"))
      (node (ref "C58") (pin "2") (pinfunction "2_2") (pintype "unspecified"))
      (node (ref "C59") (pin "2") (pinfunction "2_2") (pintype "unspecified"))
      (node (ref "C61") (pin "2") (pinfunction "2_2") (pintype "unspecified"))
      (node (ref "C62") (pin "2") (pinfunction "2_2") (pintype "unspecified"))
      (node (ref "C63") (pin "2") (pinfunction "2_2") (pintype "unspecified"))
      (node (ref "C66") (pin "1") (pinfunction "1_1") (pintype "unspecified"))
      (node (ref "C67") (pin "1") (pinfunction "1_1") (pintype "unspecified"))
      (node (ref "C68") (pin "1") (pinfunction "1_1") (pintype "unspecified"))
      (node (ref "C71") (pin "1") (pinfunction "1_1") (pintype "unspecified"))
      (node (ref "C72") (pin "1") (pinfunction "1_1") (pintype "unspecified"))
      (node (ref "C73") (pin "1") (pinfunction "1_1") (pintype "unspecified"))
      (node (ref "C74") (pin "2") (pinfunction "2_2") (pintype "unspecified"))
      (node (ref "C75") (pin "1") (pinfunction "1_1") (pintype "input"))
      (node (ref "C76") (pin "2") (pinfunction "2_2") (pintype "unspecified"))
      (node (ref "C8") (pin "2") (pinfunction "2_2") (pintype "input"))
      (node (ref "CARD1") (pin "10") (pinfunction "GND_10") (pintype "input"))
      (node (ref "CARD1") (pin "11") (pinfunction "GND_11") (pintype "input"))
      (node (ref "CARD1") (pin "12") (pinfunction "GND_12") (pintype "input"))
      (node (ref "CARD1") (pin "6") (pinfunction "VSS_6") (pintype "input"))
      (node (ref "CARD1") (pin "9") (pinfunction "GND_9") (pintype "input"))
      (node (ref "H1") (pin "6") (pinfunction "6_6") (pintype "input"))
      (node (ref "LED1") (pin "1") (pinfunction "-_1") (pintype "input"))
      (node (ref "P1") (pin "15") (pinfunction "15_15") (pintype "input"))
      (node (ref "P1") (pin "2") (pinfunction "2_2") (pintype "input"))
      (node (ref "P1") (pin "23") (pinfunction "23_23") (pintype "input"))
      (node (ref "P1") (pin "25") (pinfunction "25_25") (pintype "input"))
      (node (ref "P1") (pin "26") (pinfunction "26_26") (pintype "input"))
      (node (ref "R10") (pin "1") (pinfunction "1_1") (pintype "input"))
      (node (ref "R12") (pin "1") (pinfunction "1_1") (pintype "unspecified"))
      (node (ref "R14") (pin "1") (pinfunction "1_1") (pintype "unspecified"))
      (node (ref "R24") (pin "1") (pinfunction "1_1") (pintype "input"))
      (node (ref "R25") (pin "1") (pinfunction "1_1") (pintype "input"))
      (node (ref "R35") (pin "2") (pinfunction "2_2") (pintype "input"))
      (node (ref "R36") (pin "2") (pinfunction "2_2") (pintype "input"))
      (node (ref "R37") (pin "2") (pinfunction "2_2") (pintype "input"))
      (node (ref "R40") (pin "1") (pinfunction "1_1") (pintype "unspecified"))
      (node (ref "R42") (pin "2") (pinfunction "2_2") (pintype "input"))
      (node (ref "R43") (pin "2") (pinfunction "2_2") (pintype "input"))
      (node (ref "R45") (pin "1") (pinfunction "1_1") (pintype "unspecified"))
      (node (ref "R46") (pin "1") (pinfunction "1_1") (pintype "unspecified"))
      (node (ref "R9") (pin "1") (pinfunction "1_1") (pintype "input"))
      (node (ref "U1") (pin "A1") (pinfunction "GND_A1") (pintype "unspecified"))
      (node (ref "U1") (pin "A16") (pinfunction "GND_A16") (pintype "unspecified"))
      (node (ref "U1") (pin "D15") (pinfunction "GND_D15") (pintype "unspecified"))
      (node (ref "U1") (pin "D2") (pinfunction "GND_D2") (pintype "unspecified"))
      (node (ref "U1") (pin "F8") (pinfunction "GND_F8") (pintype "unspecified"))
      (node (ref "U1") (pin "F9") (pinfunction "GND_F9") (pintype "unspecified"))
      (node (ref "U1") (pin "G10") (pinfunction "GND_G10") (pintype "unspecified"))
      (node (ref "U1") (pin "G8") (pinfunction "GND_G8") (pintype "unspecified"))
      (node (ref "U1") (pin "H1") (pinfunction "GND_H1") (pintype "unspecified"))
      (node (ref "U1") (pin "H10") (pinfunction "GND_H10") (pintype "unspecified"))
      (node (ref "U1") (pin "H16") (pinfunction "GND_H16") (pintype "unspecified"))
      (node (ref "U1") (pin "H8") (pinfunction "GND_H8") (pintype "unspecified"))
      (node (ref "U1") (pin "H9") (pinfunction "GND_H9") (pintype "unspecified"))
      (node (ref "U1") (pin "J10") (pinfunction "GND_J10") (pintype "unspecified"))
      (node (ref "U1") (pin "J8") (pinfunction "GND_J8") (pintype "unspecified"))
      (node (ref "U1") (pin "J9") (pinfunction "GND_J9") (pintype "unspecified"))
      (node (ref "U1") (pin "K10") (pinfunction "GND_K10") (pintype "unspecified"))
      (node (ref "U1") (pin "K6") (pinfunction "GND_K6") (pintype "unspecified"))
      (node (ref "U1") (pin "K7") (pinfunction "GND_K7") (pintype "unspecified"))
      (node (ref "U1") (pin "K8") (pinfunction "GND_K8") (pintype "unspecified"))
      (node (ref "U1") (pin "K9") (pinfunction "GND_K9") (pintype "unspecified"))
      (node (ref "U1") (pin "N15") (pinfunction "GND_N15") (pintype "unspecified"))
      (node (ref "U1") (pin "N2") (pinfunction "GND_N2") (pintype "unspecified"))
      (node (ref "U1") (pin "T1") (pinfunction "GND_T1") (pintype "unspecified"))
      (node (ref "U1") (pin "T12") (pinfunction "GND_T12") (pintype "unspecified"))
      (node (ref "U1") (pin "T16") (pinfunction "GND_T16") (pintype "unspecified"))
      (node (ref "U1") (pin "T5") (pinfunction "GND_T5") (pintype "unspecified"))
      (node (ref "U10") (pin "2") (pinfunction "2_2") (pintype "unspecified"))
      (node (ref "U10") (pin "4") (pinfunction "4_4") (pintype "unspecified"))
      (node (ref "U11") (pin "4") (pinfunction "GND_4") (pintype "unspecified"))
      (node (ref "U12") (pin "4") (pinfunction "GND_4") (pintype "unspecified"))
      (node (ref "U2") (pin "1") (pinfunction "GND_1") (pintype "unspecified"))
      (node (ref "U2") (pin "40") (pinfunction "GND_40") (pintype "unspecified"))
      (node (ref "U2") (pin "41") (pinfunction "GND_41") (pintype "unspecified"))
      (node (ref "U5") (pin "12") (pinfunction "VSSQ_12") (pintype "unspecified"))
      (node (ref "U5") (pin "28") (pinfunction "VSS_28") (pintype "unspecified"))
      (node (ref "U5") (pin "41") (pinfunction "VSS_41") (pintype "unspecified"))
      (node (ref "U5") (pin "46") (pinfunction "VSSQ_46") (pintype "unspecified"))
      (node (ref "U5") (pin "52") (pinfunction "VSSQ_52") (pintype "unspecified"))
      (node (ref "U5") (pin "54") (pinfunction "VSS_54") (pintype "unspecified"))
      (node (ref "U5") (pin "6") (pinfunction "VSSQ_6") (pintype "unspecified"))
      (node (ref "U6") (pin "4") (pinfunction "GND_4") (pintype "unspecified"))
      (node (ref "U7") (pin "4") (pinfunction "GND_4") (pintype "unspecified"))
      (node (ref "U8") (pin "1") (pinfunction "GND_1") (pintype "unspecified"))
      (node (ref "U9") (pin "2") (pinfunction "GND_2") (pintype "unspecified"))
      (node (ref "USB1") (pin "1") (pinfunction "SHELL_1") (pintype "unspecified"))
      (node (ref "USB1") (pin "2") (pinfunction "SHELL_2") (pintype "unspecified"))
      (node (ref "USB1") (pin "3") (pinfunction "SHELL_3") (pintype "unspecified"))
      (node (ref "USB1") (pin "4") (pinfunction "SHELL_4") (pintype "unspecified"))
      (node (ref "USB1") (pin "A1B12") (pinfunction "GND_A1B12") (pintype "unspecified"))
      (node (ref "USB1") (pin "B1A12") (pinfunction "GND_B1A12") (pintype "unspecified"))
      (node (ref "USB2") (pin "1") (pinfunction "SHELL_1") (pintype "unspecified"))
      (node (ref "USB2") (pin "2") (pinfunction "SHELL_2") (pintype "unspecified"))
      (node (ref "USB2") (pin "3") (pinfunction "SHELL_3") (pintype "unspecified"))
      (node (ref "USB2") (pin "4") (pinfunction "SHELL_4") (pintype "unspecified"))
      (node (ref "USB2") (pin "A1B12") (pinfunction "GND_A1B12") (pintype "unspecified"))
      (node (ref "USB2") (pin "B1A12") (pinfunction "GND_B1A12") (pintype "unspecified"))
    )
    (net (code "25") (name "HREF") (class "Default")
      (node (ref "R75") (pin "1") (pinfunction "1_1") (pintype "input"))
      (node (ref "U1") (pin "A11") (pinfunction "PT53A_A11") (pintype "unspecified"))
    )
    (net (code "26") (name "INITN") (class "Default")
      (node (ref "R5") (pin "1") (pinfunction "1_1") (pintype "input"))
      (node (ref "U1") (pin "T9") (pinfunction "INITN_T9") (pintype "unspecified"))
      (node (ref "U2") (pin "8") (pinfunction "IO15_8") (pintype "unspecified"))
    )
    (net (code "27") (name "MCLK") (class "Default")
      (node (ref "R77") (pin "1") (pinfunction "1_1") (pintype "input"))
      (node (ref "U1") (pin "A12") (pinfunction "PT53B_A12") (pintype "unspecified"))
    )
    (net (code "28") (name "M_CLK") (class "Default")
      (node (ref "CARD1") (pin "5") (pinfunction "CLK_5") (pintype "input"))
      (node (ref "U1") (pin "C7") (pinfunction "PT27A_C7") (pintype "unspecified"))
    )
    (net (code "29") (name "M_CMD") (class "Default")
      (node (ref "CARD1") (pin "3") (pinfunction "CMD_3") (pintype "input"))
      (node (ref "R20") (pin "1") (pinfunction "1_1") (pintype "unspecified"))
      (node (ref "U1") (pin "B4") (pinfunction "PT11B_B4") (pintype "unspecified"))
    )
    (net (code "30") (name "M_D0") (class "Default")
      (node (ref "CARD1") (pin "7") (pinfunction "D0_7") (pintype "input"))
      (node (ref "R18") (pin "1") (pinfunction "1_1") (pintype "unspecified"))
      (node (ref "U1") (pin "B2") (pinfunction "PL2B_B2") (pintype "unspecified"))
    )
    (net (code "31") (name "M_D1") (class "Default")
      (node (ref "CARD1") (pin "8") (pinfunction "D1_8") (pintype "input"))
      (node (ref "R19") (pin "1") (pinfunction "1_1") (pintype "unspecified"))
      (node (ref "U1") (pin "B1") (pinfunction "PL2A_B1") (pintype "unspecified"))
    )
    (net (code "32") (name "M_D2") (class "Default")
      (node (ref "CARD1") (pin "1") (pinfunction "D2_1") (pintype "input"))
      (node (ref "R16") (pin "1") (pinfunction "1_1") (pintype "unspecified"))
      (node (ref "U1") (pin "B6") (pinfunction "PT22B_B6") (pintype "unspecified"))
    )
    (net (code "33") (name "M_D3") (class "Default")
      (node (ref "CARD1") (pin "2") (pinfunction "D3_2") (pintype "input"))
      (node (ref "R17") (pin "1") (pinfunction "1_1") (pintype "unspecified"))
      (node (ref "U1") (pin "B5") (pinfunction "PT15B_B5") (pintype "unspecified"))
    )
    (net (code "34") (name "Net-(C29-Pad2)") (class "Default")
      (node (ref "C29") (pin "2") (pinfunction "2_2") (pintype "unspecified"))
      (node (ref "C30") (pin "2") (pinfunction "2_2") (pintype "unspecified"))
      (node (ref "C31") (pin "1") (pinfunction "1_1") (pintype "input"))
      (node (ref "C32") (pin "1") (pinfunction "1_1") (pintype "input"))
    )
    (net (code "35") (name "Net-(LED1-+)") (class "Default")
      (node (ref "LED1") (pin "2") (pinfunction "+_2") (pintype "input"))
      (node (ref "R89") (pin "2") (pinfunction "2_2") (pintype "input"))
    )
    (net (code "36") (name "Net-(P1-Pad3)") (class "Default")
      (node (ref "P1") (pin "3") (pinfunction "3_3") (pintype "input"))
      (node (ref "R38") (pin "1") (pinfunction "1_1") (pintype "input"))
      (node (ref "R71") (pin "2") (pinfunction "2_2") (pintype "input"))
    )
    (net (code "37") (name "Net-(P1-Pad5)") (class "Default")
      (node (ref "P1") (pin "5") (pinfunction "5_5") (pintype "input"))
      (node (ref "R39") (pin "1") (pinfunction "1_1") (pintype "input"))
      (node (ref "R72") (pin "2") (pinfunction "2_2") (pintype "input"))
    )
    (net (code "38") (name "Net-(P1-Pad7)") (class "Default")
      (node (ref "P1") (pin "7") (pinfunction "7_7") (pintype "input"))
      (node (ref "R73") (pin "2") (pinfunction "2_2") (pintype "input"))
    )
    (net (code "39") (name "Net-(P1-Pad8)") (class "Default")
      (node (ref "P1") (pin "8") (pinfunction "8_8") (pintype "input"))
      (node (ref "R35") (pin "1") (pinfunction "1_1") (pintype "input"))
    )
    (net (code "40") (name "Net-(P1-Pad9)") (class "Default")
      (node (ref "P1") (pin "9") (pinfunction "9_9") (pintype "input"))
      (node (ref "R75") (pin "2") (pinfunction "2_2") (pintype "input"))
    )
    (net (code "41") (name "Net-(P1-Pad12)") (class "Default")
      (node (ref "P1") (pin "12") (pinfunction "12_12") (pintype "input"))
      (node (ref "R76") (pin "2") (pinfunction "2_2") (pintype "input"))
    )
    (net (code "42") (name "Net-(P1-Pad13)") (class "Default")
      (node (ref "P1") (pin "13") (pinfunction "13_13") (pintype "input"))
      (node (ref "R77") (pin "2") (pinfunction "2_2") (pintype "input"))
    )
    (net (code "43") (name "Net-(P1-Pad14)") (class "Default")
      (node (ref "P1") (pin "14") (pinfunction "14_14") (pintype "input"))
      (node (ref "R78") (pin "2") (pinfunction "2_2") (pintype "input"))
    )
    (net (code "44") (name "Net-(P1-Pad16)") (class "Default")
      (node (ref "P1") (pin "16") (pinfunction "16_16") (pintype "input"))
      (node (ref "R79") (pin "2") (pinfunction "2_2") (pintype "input"))
    )
    (net (code "45") (name "Net-(P1-Pad17)") (class "Default")
      (node (ref "P1") (pin "17") (pinfunction "17_17") (pintype "input"))
      (node (ref "R80") (pin "2") (pinfunction "2_2") (pintype "input"))
    )
    (net (code "46") (name "Net-(P1-Pad18)") (class "Default")
      (node (ref "P1") (pin "18") (pinfunction "18_18") (pintype "input"))
      (node (ref "R81") (pin "2") (pinfunction "2_2") (pintype "input"))
    )
    (net (code "47") (name "Net-(P1-Pad19)") (class "Default")
      (node (ref "P1") (pin "19") (pinfunction "19_19") (pintype "input"))
      (node (ref "R82") (pin "2") (pinfunction "2_2") (pintype "input"))
    )
    (net (code "48") (name "Net-(P1-Pad20)") (class "Default")
      (node (ref "P1") (pin "20") (pinfunction "20_20") (pintype "input"))
      (node (ref "R83") (pin "2") (pinfunction "2_2") (pintype "input"))
    )
    (net (code "49") (name "Net-(P1-Pad21)") (class "Default")
      (node (ref "P1") (pin "21") (pinfunction "21_21") (pintype "input"))
      (node (ref "R84") (pin "2") (pinfunction "2_2") (pintype "input"))
    )
    (net (code "50") (name "Net-(P1-Pad22)") (class "Default")
      (node (ref "P1") (pin "22") (pinfunction "22_22") (pintype "input"))
      (node (ref "R85") (pin "2") (pinfunction "2_2") (pintype "input"))
    )
    (net (code "51") (name "Net-(R44-Pad2)") (class "Default")
      (node (ref "R44") (pin "2") (pinfunction "2_2") (pintype "unspecified"))
      (node (ref "USB2") (pin "A4B9") (pinfunction "VBUS_A4B9") (pintype "unspecified"))
      (node (ref "USB2") (pin "B4A9") (pinfunction "VBUS_B4A9") (pintype "unspecified"))
    )
    (net (code "52") (name "Net-(U1B-CFG_0)") (class "Default")
      (node (ref "R24") (pin "2") (pinfunction "2_2") (pintype "input"))
      (node (ref "U1") (pin "N10") (pinfunction "CFG_0_N10") (pintype "unspecified"))
    )
    (net (code "53") (name "Net-(U1B-CFG_1)") (class "Default")
      (node (ref "R23") (pin "2") (pinfunction "2_2") (pintype "input"))
      (node (ref "U1") (pin "P10") (pinfunction "CFG_1_P10") (pintype "unspecified"))
    )
    (net (code "54") (name "Net-(U1B-CFG_2)") (class "Default")
      (node (ref "R25") (pin "2") (pinfunction "2_2") (pintype "input"))
      (node (ref "U1") (pin "R10") (pinfunction "CFG_2_R10") (pintype "unspecified"))
    )
    (net (code "55") (name "Net-(U1B-PL32B)") (class "Default")
      (node (ref "TP2") (pin "1") (pinfunction "1_1") (pintype "input"))
      (node (ref "U1") (pin "P2") (pinfunction "PL32B_P2") (pintype "unspecified"))
    )
    (net (code "56") (name "Net-(U1B-PL35A)") (class "Default")
      (node (ref "TP1") (pin "1") (pinfunction "1_1") (pintype "input"))
      (node (ref "U1") (pin "P1") (pinfunction "PL35A_P1") (pintype "unspecified"))
    )
    (net (code "57") (name "Net-(U1B-PL38B)") (class "Default")
      (node (ref "TP3") (pin "1") (pinfunction "1_1") (pintype "input"))
      (node (ref "U1") (pin "P3") (pinfunction "PL38B_P3") (pintype "unspecified"))
    )
    (net (code "58") (name "Net-(U1B-PL41A)") (class "Default")
      (node (ref "TP4") (pin "1") (pinfunction "1_1") (pintype "input"))
      (node (ref "U1") (pin "P4") (pinfunction "PL41A_P4") (pintype "unspecified"))
    )
    (net (code "59") (name "Net-(U1B-PL47D)") (class "Default")
      (node (ref "TP6") (pin "1") (pinfunction "1_1") (pintype "input"))
      (node (ref "U1") (pin "P5") (pinfunction "PL47D_P5") (pintype "unspecified"))
    )
    (net (code "60") (name "Net-(U2-EN)") (class "Default")
      (node (ref "R7") (pin "1") (pinfunction "1_1") (pintype "input"))
      (node (ref "U2") (pin "3") (pinfunction "EN_3") (pintype "unspecified"))
    )
    (net (code "61") (name "Net-(U2-IO5)") (class "Default")
      (node (ref "R26") (pin "2") (pinfunction "2_2") (pintype "input"))
      (node (ref "U2") (pin "5") (pinfunction "IO5_5") (pintype "unspecified"))
    )
    (net (code "62") (name "Net-(U2-IO6)") (class "Default")
      (node (ref "R27") (pin "2") (pinfunction "2_2") (pintype "input"))
      (node (ref "U2") (pin "6") (pinfunction "IO6_6") (pintype "unspecified"))
    )
    (net (code "63") (name "Net-(U2-IO7)") (class "Default")
      (node (ref "R28") (pin "2") (pinfunction "2_2") (pintype "input"))
      (node (ref "U2") (pin "7") (pinfunction "IO7_7") (pintype "unspecified"))
    )
    (net (code "64") (name "Net-(U2-IO8)") (class "Default")
      (node (ref "R30") (pin "2") (pinfunction "2_2") (pintype "input"))
      (node (ref "U2") (pin "12") (pinfunction "IO8_12") (pintype "unspecified"))
    )
    (net (code "65") (name "Net-(U2-IO10)") (class "Default")
      (node (ref "R86") (pin "2") (pinfunction "2_2") (pintype "input"))
      (node (ref "U2") (pin "18") (pinfunction "IO10_18") (pintype "unspecified"))
    )
    (net (code "66") (name "Net-(U2-IO11)") (class "Default")
      (node (ref "R6") (pin "2") (pinfunction "2_2") (pintype "input"))
      (node (ref "U2") (pin "19") (pinfunction "IO11_19") (pintype "unspecified"))
    )
    (net (code "67") (name "Net-(U2-IO12)") (class "Default")
      (node (ref "R87") (pin "2") (pinfunction "2_2") (pintype "input"))
      (node (ref "U2") (pin "20") (pinfunction "IO12_20") (pintype "unspecified"))
    )
    (net (code "68") (name "Net-(U2-IO13)") (class "Default")
      (node (ref "R88") (pin "2") (pinfunction "2_2") (pintype "input"))
      (node (ref "U2") (pin "21") (pinfunction "IO13_21") (pintype "unspecified"))
    )
    (net (code "69") (name "Net-(U2-IO16)") (class "Default")
      (node (ref "R29") (pin "2") (pinfunction "2_2") (pintype "input"))
      (node (ref "U2") (pin "9") (pinfunction "IO16_9") (pintype "unspecified"))
    )
    (net (code "70") (name "Net-(U2-IO21)") (class "Default")
      (node (ref "R31") (pin "2") (pinfunction "2_2") (pintype "input"))
      (node (ref "U2") (pin "23") (pinfunction "IO21_23") (pintype "unspecified"))
    )
    (net (code "71") (name "Net-(U2-IO47)") (class "Default")
      (node (ref "R32") (pin "2") (pinfunction "2_2") (pintype "input"))
      (node (ref "U2") (pin "24") (pinfunction "IO47_24") (pintype "unspecified"))
    )
    (net (code "72") (name "Net-(U2-IO48)") (class "Default")
      (node (ref "R34") (pin "2") (pinfunction "2_2") (pintype "input"))
      (node (ref "U2") (pin "25") (pinfunction "IO48_25") (pintype "unspecified"))
    )
    (net (code "73") (name "Net-(U5-A0)") (class "Default")
      (node (ref "R56") (pin "2") (pinfunction "2_2") (pintype "input"))
      (node (ref "U5") (pin "23") (pinfunction "A0_23") (pintype "unspecified"))
    )
    (net (code "74") (name "Net-(U5-A1)") (class "Default")
      (node (ref "R57") (pin "2") (pinfunction "2_2") (pintype "input"))
      (node (ref "U5") (pin "24") (pinfunction "A1_24") (pintype "unspecified"))
    )
    (net (code "75") (name "Net-(U5-A2)") (class "Default")
      (node (ref "R58") (pin "2") (pinfunction "2_2") (pintype "input"))
      (node (ref "U5") (pin "25") (pinfunction "A2_25") (pintype "unspecified"))
    )
    (net (code "76") (name "Net-(U5-A3)") (class "Default")
      (node (ref "R59") (pin "2") (pinfunction "2_2") (pintype "input"))
      (node (ref "U5") (pin "26") (pinfunction "A3_26") (pintype "unspecified"))
    )
    (net (code "77") (name "Net-(U5-A4)") (class "Default")
      (node (ref "R68") (pin "1") (pinfunction "1_1") (pintype "input"))
      (node (ref "U5") (pin "29") (pinfunction "A4_29") (pintype "unspecified"))
    )
    (net (code "78") (name "Net-(U5-A5)") (class "Default")
      (node (ref "R67") (pin "1") (pinfunction "1_1") (pintype "input"))
      (node (ref "U5") (pin "30") (pinfunction "A5_30") (pintype "unspecified"))
    )
    (net (code "79") (name "Net-(U5-A6)") (class "Default")
      (node (ref "R66") (pin "1") (pinfunction "1_1") (pintype "input"))
      (node (ref "U5") (pin "31") (pinfunction "A6_31") (pintype "unspecified"))
    )
    (net (code "80") (name "Net-(U5-A7)") (class "Default")
      (node (ref "R65") (pin "1") (pinfunction "1_1") (pintype "input"))
      (node (ref "U5") (pin "32") (pinfunction "A7_32") (pintype "unspecified"))
    )
    (net (code "81") (name "Net-(U5-A8)") (class "Default")
      (node (ref "R64") (pin "1") (pinfunction "1_1") (pintype "input"))
      (node (ref "U5") (pin "33") (pinfunction "A8_33") (pintype "unspecified"))
    )
    (net (code "82") (name "Net-(U5-A9)") (class "Default")
      (node (ref "R63") (pin "1") (pinfunction "1_1") (pintype "input"))
      (node (ref "U5") (pin "34") (pinfunction "A9_34") (pintype "unspecified"))
    )
    (net (code "83") (name "Net-(U5-A10{slash}AP)") (class "Default")
      (node (ref "R55") (pin "2") (pinfunction "2_2") (pintype "input"))
      (node (ref "U5") (pin "22") (pinfunction "A10/AP_22") (pintype "unspecified"))
    )
    (net (code "84") (name "Net-(U5-A11)") (class "Default")
      (node (ref "R62") (pin "1") (pinfunction "1_1") (pintype "input"))
      (node (ref "U5") (pin "35") (pinfunction "A11_35") (pintype "unspecified"))
    )
    (net (code "85") (name "Net-(U5-A12)") (class "Default")
      (node (ref "R61") (pin "1") (pinfunction "1_1") (pintype "input"))
      (node (ref "U5") (pin "36") (pinfunction "A12_36") (pintype "unspecified"))
    )
    (net (code "86") (name "Net-(U5-BS0)") (class "Default")
      (node (ref "R54") (pin "2") (pinfunction "2_2") (pintype "input"))
      (node (ref "U5") (pin "20") (pinfunction "BS0_20") (pintype "unspecified"))
    )
    (net (code "87") (name "Net-(U5-BS1)") (class "Default")
      (node (ref "R53") (pin "2") (pinfunction "2_2") (pintype "input"))
      (node (ref "U5") (pin "21") (pinfunction "BS1_21") (pintype "unspecified"))
    )
    (net (code "88") (name "Net-(U5-CAS#)") (class "Default")
      (node (ref "R49") (pin "2") (pinfunction "2_2") (pintype "input"))
      (node (ref "U5") (pin "17") (pinfunction "CAS#_17") (pintype "unspecified"))
    )
    (net (code "89") (name "Net-(U5-CKE)") (class "Default")
      (node (ref "R1") (pin "1") (pinfunction "1_1") (pintype "input"))
      (node (ref "U5") (pin "37") (pinfunction "CKE_37") (pintype "unspecified"))
    )
    (net (code "90") (name "Net-(U5-CLK)") (class "Default")
      (node (ref "R2") (pin "1") (pinfunction "1_1") (pintype "input"))
      (node (ref "U5") (pin "38") (pinfunction "CLK_38") (pintype "unspecified"))
    )
    (net (code "91") (name "Net-(U5-CS#)") (class "Default")
      (node (ref "R51") (pin "2") (pinfunction "2_2") (pintype "input"))
      (node (ref "U5") (pin "19") (pinfunction "CS#_19") (pintype "unspecified"))
    )
    (net (code "92") (name "Net-(U5-LDQM)") (class "Default")
      (node (ref "R69") (pin "2") (pinfunction "2_2") (pintype "input"))
      (node (ref "U5") (pin "15") (pinfunction "LDQM_15") (pintype "unspecified"))
    )
    (net (code "93") (name "Net-(U5-RAS#)") (class "Default")
      (node (ref "R50") (pin "2") (pinfunction "2_2") (pintype "input"))
      (node (ref "U5") (pin "18") (pinfunction "RAS#_18") (pintype "unspecified"))
    )
    (net (code "94") (name "Net-(U5-UDQM)") (class "Default")
      (node (ref "R70") (pin "1") (pinfunction "1_1") (pintype "input"))
      (node (ref "U5") (pin "39") (pinfunction "UDQM_39") (pintype "unspecified"))
    )
    (net (code "95") (name "Net-(U5-WE#)") (class "Default")
      (node (ref "R48") (pin "2") (pinfunction "2_2") (pintype "input"))
      (node (ref "U5") (pin "16") (pinfunction "WE#_16") (pintype "unspecified"))
    )
    (net (code "96") (name "Net-(U6-BST)") (class "Default")
      (node (ref "C18") (pin "1") (pinfunction "1_1") (pintype "unspecified"))
      (node (ref "U6") (pin "6") (pinfunction "BST_6") (pintype "unspecified"))
    )
    (net (code "97") (name "Net-(U6-FB)") (class "Default")
      (node (ref "C19") (pin "1") (pinfunction "1_1") (pintype "unspecified"))
      (node (ref "R11") (pin "1") (pinfunction "1_1") (pintype "unspecified"))
      (node (ref "R12") (pin "2") (pinfunction "2_2") (pintype "unspecified"))
      (node (ref "U6") (pin "1") (pinfunction "FB_1") (pintype "unspecified"))
    )
    (net (code "98") (name "Net-(U6-SW)") (class "Default")
      (node (ref "C18") (pin "2") (pinfunction "2_2") (pintype "unspecified"))
      (node (ref "L1") (pin "1") (pinfunction "1_1") (pintype "unspecified"))
      (node (ref "U6") (pin "5") (pinfunction "SW_5") (pintype "unspecified"))
    )
    (net (code "99") (name "Net-(U7-BST)") (class "Default")
      (node (ref "C24") (pin "1") (pinfunction "1_1") (pintype "unspecified"))
      (node (ref "U7") (pin "6") (pinfunction "BST_6") (pintype "unspecified"))
    )
    (net (code "100") (name "Net-(U7-FB)") (class "Default")
      (node (ref "C25") (pin "1") (pinfunction "1_1") (pintype "unspecified"))
      (node (ref "R14") (pin "2") (pinfunction "2_2") (pintype "unspecified"))
      (node (ref "R15") (pin "1") (pinfunction "1_1") (pintype "input"))
      (node (ref "U7") (pin "1") (pinfunction "FB_1") (pintype "unspecified"))
    )
    (net (code "101") (name "Net-(U7-SW)") (class "Default")
      (node (ref "C24") (pin "2") (pinfunction "2_2") (pintype "unspecified"))
      (node (ref "L2") (pin "1") (pinfunction "1_1") (pintype "unspecified"))
      (node (ref "U7") (pin "5") (pinfunction "SW_5") (pintype "unspecified"))
    )
    (net (code "102") (name "Net-(U11-BST)") (class "Default")
      (node (ref "C64") (pin "1") (pinfunction "1_1") (pintype "unspecified"))
      (node (ref "U11") (pin "6") (pinfunction "BST_6") (pintype "unspecified"))
    )
    (net (code "103") (name "Net-(U11-FB)") (class "Default")
      (node (ref "C65") (pin "1") (pinfunction "1_1") (pintype "unspecified"))
      (node (ref "R40") (pin "2") (pinfunction "2_2") (pintype "unspecified"))
      (node (ref "R41") (pin "1") (pinfunction "1_1") (pintype "unspecified"))
      (node (ref "U11") (pin "1") (pinfunction "FB_1") (pintype "unspecified"))
    )
    (net (code "104") (name "Net-(U11-SW)") (class "Default")
      (node (ref "C64") (pin "2") (pinfunction "2_2") (pintype "unspecified"))
      (node (ref "L3") (pin "1") (pinfunction "1_1") (pintype "unspecified"))
      (node (ref "U11") (pin "5") (pinfunction "SW_5") (pintype "unspecified"))
    )
    (net (code "105") (name "Net-(U12-BST)") (class "Default")
      (node (ref "C69") (pin "1") (pinfunction "1_1") (pintype "unspecified"))
      (node (ref "U12") (pin "6") (pinfunction "BST_6") (pintype "unspecified"))
    )
    (net (code "106") (name "Net-(U12-FB)") (class "Default")
      (node (ref "C70") (pin "1") (pinfunction "1_1") (pintype "unspecified"))
      (node (ref "R46") (pin "2") (pinfunction "2_2") (pintype "unspecified"))
      (node (ref "R47") (pin "1") (pinfunction "1_1") (pintype "input"))
      (node (ref "U12") (pin "1") (pinfunction "FB_1") (pintype "unspecified"))
    )
    (net (code "107") (name "Net-(U12-SW)") (class "Default")
      (node (ref "C69") (pin "2") (pinfunction "2_2") (pintype "unspecified"))
      (node (ref "L4") (pin "1") (pinfunction "1_1") (pintype "unspecified"))
      (node (ref "U12") (pin "5") (pinfunction "SW_5") (pintype "unspecified"))
    )
    (net (code "108") (name "Net-(USB1-CC1)") (class "Default")
      (node (ref "R9") (pin "2") (pinfunction "2_2") (pintype "input"))
      (node (ref "USB1") (pin "A5") (pinfunction "CC1_A5") (pintype "unspecified"))
    )
    (net (code "109") (name "Net-(USB1-CC2)") (class "Default")
      (node (ref "R10") (pin "2") (pinfunction "2_2") (pintype "input"))
      (node (ref "USB1") (pin "B5") (pinfunction "CC2_B5") (pintype "unspecified"))
    )
    (net (code "110") (name "Net-(USB2-CC1)") (class "Default")
      (node (ref "R43") (pin "1") (pinfunction "1_1") (pintype "input"))
      (node (ref "USB2") (pin "A5") (pinfunction "CC1_A5") (pintype "unspecified"))
    )
    (net (code "111") (name "Net-(USB2-CC2)") (class "Default")
      (node (ref "R42") (pin "1") (pinfunction "1_1") (pintype "input"))
      (node (ref "USB2") (pin "B5") (pinfunction "CC2_B5") (pintype "unspecified"))
    )
    (net (code "112") (name "PCLK") (class "Default")
      (node (ref "R80") (pin "1") (pinfunction "1_1") (pintype "input"))
      (node (ref "U1") (pin "C8") (pinfunction "PT35A_C8") (pintype "unspecified"))
    )
    (net (code "113") (name "PROGRAM") (class "Default")
      (node (ref "R37") (pin "1") (pinfunction "1_1") (pintype "input"))
      (node (ref "U10") (pin "3") (pinfunction "3_3") (pintype "unspecified"))
      (node (ref "U2") (pin "27") (pinfunction "IO0_27") (pintype "unspecified"))
    )
    (net (code "114") (name "PROGRAMN") (class "Default")
      (node (ref "R4") (pin "2") (pinfunction "2_2") (pintype "input"))
      (node (ref "U1") (pin "R9") (pinfunction "PROGRAMN_R9") (pintype "unspecified"))
      (node (ref "U2") (pin "17") (pinfunction "IO9_17") (pintype "unspecified"))
    )
    (net (code "115") (name "RESET") (class "Default")
      (node (ref "P1") (pin "6") (pinfunction "6_6") (pintype "input"))
      (node (ref "R36") (pin "1") (pinfunction "1_1") (pintype "input"))
      (node (ref "U10") (pin "1") (pinfunction "1_1") (pintype "unspecified"))
      (node (ref "U2") (pin "31") (pinfunction "IO38_31") (pintype "unspecified"))
    )
    (net (code "116") (name "RX") (class "Default")
      (node (ref "U1") (pin "K1") (pinfunction "PL23C_K1") (pintype "unspecified"))
      (node (ref "U2") (pin "36") (pinfunction "RXD0_36") (pintype "unspecified"))
    )
    (net (code "117") (name "SCL") (class "Default")
      (node (ref "R21") (pin "1") (pinfunction "1_1") (pintype "input"))
      (node (ref "U2") (pin "10") (pinfunction "IO17_10") (pintype "unspecified"))
    )
    (net (code "118") (name "SDA") (class "Default")
      (node (ref "R22") (pin "1") (pinfunction "1_1") (pintype "input"))
      (node (ref "U2") (pin "11") (pinfunction "IO18_11") (pintype "unspecified"))
    )
    (net (code "119") (name "SD_A0") (class "Default")
      (node (ref "R56") (pin "1") (pinfunction "1_1") (pintype "input"))
      (node (ref "U1") (pin "T6") (pinfunction "PB4A_T6") (pintype "unspecified"))
    )
    (net (code "120") (name "SD_A1") (class "Default")
      (node (ref "R57") (pin "1") (pinfunction "1_1") (pintype "input"))
      (node (ref "U1") (pin "T4") (pinfunction "PL44B_T4") (pintype "unspecified"))
    )
    (net (code "121") (name "SD_A2") (class "Default")
      (node (ref "R58") (pin "1") (pinfunction "1_1") (pintype "input"))
      (node (ref "U1") (pin "T3") (pinfunction "PL41D_T3") (pintype "unspecified"))
    )
    (net (code "122") (name "SD_A3") (class "Default")
      (node (ref "R59") (pin "1") (pinfunction "1_1") (pintype "input"))
      (node (ref "U1") (pin "T2") (pinfunction "PL38D_T2") (pintype "unspecified"))
    )
    (net (code "123") (name "SD_A4") (class "Default")
      (node (ref "R68") (pin "2") (pinfunction "2_2") (pintype "input"))
      (node (ref "U1") (pin "A2") (pinfunction "PT4A_A2") (pintype "unspecified"))
    )
    (net (code "124") (name "SD_A5") (class "Default")
      (node (ref "R67") (pin "2") (pinfunction "2_2") (pintype "input"))
      (node (ref "U1") (pin "A3") (pinfunction "PT6A_A3") (pintype "unspecified"))
    )
    (net (code "125") (name "SD_A6") (class "Default")
      (node (ref "R66") (pin "2") (pinfunction "2_2") (pintype "input"))
      (node (ref "U1") (pin "A4") (pinfunction "PT6B_A4") (pintype "unspecified"))
    )
    (net (code "126") (name "SD_A7") (class "Default")
      (node (ref "R65") (pin "2") (pinfunction "2_2") (pintype "input"))
      (node (ref "U1") (pin "A5") (pinfunction "PT18A_A5") (pintype "unspecified"))
    )
    (net (code "127") (name "SD_A8") (class "Default")
      (node (ref "R64") (pin "2") (pinfunction "2_2") (pintype "input"))
      (node (ref "U1") (pin "A6") (pinfunction "PT18B_A6") (pintype "unspecified"))
    )
    (net (code "128") (name "SD_A9") (class "Default")
      (node (ref "R63") (pin "2") (pinfunction "2_2") (pintype "input"))
      (node (ref "U1") (pin "A7") (pinfunction "PT29A_A7") (pintype "unspecified"))
    )
    (net (code "129") (name "SD_A10") (class "Default")
      (node (ref "R55") (pin "1") (pinfunction "1_1") (pintype "input"))
      (node (ref "U1") (pin "T7") (pinfunction "PB11A_T7") (pintype "unspecified"))
    )
    (net (code "130") (name "SD_A11") (class "Default")
      (node (ref "R62") (pin "2") (pinfunction "2_2") (pintype "input"))
      (node (ref "U1") (pin "A8") (pinfunction "PT29B_A8") (pintype "unspecified"))
    )
    (net (code "131") (name "SD_A12") (class "Default")
      (node (ref "R61") (pin "2") (pinfunction "2_2") (pintype "input"))
      (node (ref "U1") (pin "B7") (pinfunction "PT27B_B7") (pintype "unspecified"))
    )
    (net (code "132") (name "SD_BA0") (class "Default")
      (node (ref "R54") (pin "1") (pinfunction "1_1") (pintype "input"))
      (node (ref "U1") (pin "K12") (pinfunction "PR29B_K12") (pintype "unspecified"))
    )
    (net (code "133") (name "SD_BA1") (class "Default")
      (node (ref "R53") (pin "1") (pinfunction "1_1") (pintype "input"))
      (node (ref "U1") (pin "L12") (pinfunction "PR29D_L12") (pintype "unspecified"))
    )
    (net (code "134") (name "SD_CAS_N") (class "Default")
      (node (ref "R49") (pin "1") (pinfunction "1_1") (pintype "input"))
      (node (ref "U1") (pin "R13") (pinfunction "PR41C_R13") (pintype "unspecified"))
    )
    (net (code "135") (name "SD_CLK") (class "Default")
      (node (ref "R2") (pin "2") (pinfunction "2_2") (pintype "input"))
      (node (ref "U1") (pin "J15") (pinfunction "PR23B_J15") (pintype "unspecified"))
    )
    (net (code "136") (name "SD_CS_N") (class "Default")
      (node (ref "R51") (pin "1") (pinfunction "1_1") (pintype "input"))
      (node (ref "U1") (pin "R15") (pinfunction "PR38C_R15") (pintype "unspecified"))
    )
    (net (code "137") (name "SD_DQ0") (class "Default")
      (node (ref "U1") (pin "L15") (pinfunction "PR26B_L15") (pintype "unspecified"))
      (node (ref "U5") (pin "2") (pinfunction "DQ0_2") (pintype "unspecified"))
    )
    (net (code "138") (name "SD_DQ1") (class "Default")
      (node (ref "U1") (pin "M16") (pinfunction "PR26C_M16") (pintype "unspecified"))
      (node (ref "U5") (pin "4") (pinfunction "DQ1_4") (pintype "unspecified"))
    )
    (net (code "139") (name "SD_DQ2") (class "Default")
      (node (ref "U1") (pin "K16") (pinfunction "PR23C_K16") (pintype "unspecified"))
      (node (ref "U5") (pin "5") (pinfunction "DQ2_5") (pintype "unspecified"))
    )
    (net (code "140") (name "SD_DQ3") (class "Default")
      (node (ref "U1") (pin "M15") (pinfunction "PR26D_M15") (pintype "unspecified"))
      (node (ref "U5") (pin "7") (pinfunction "DQ3_7") (pintype "unspecified"))
    )
    (net (code "141") (name "SD_DQ4") (class "Default")
      (node (ref "U1") (pin "M14") (pinfunction "PR32D_M14") (pintype "unspecified"))
      (node (ref "U5") (pin "8") (pinfunction "DQ4_8") (pintype "unspecified"))
    )
    (net (code "142") (name "SD_DQ5") (class "Default")
      (node (ref "U1") (pin "P16") (pinfunction "PR35A_P16") (pintype "unspecified"))
      (node (ref "U5") (pin "10") (pinfunction "DQ5_10") (pintype "unspecified"))
    )
    (net (code "143") (name "SD_DQ6") (class "Default")
      (node (ref "U1") (pin "R16") (pinfunction "PR35B_R16") (pintype "unspecified"))
      (node (ref "U5") (pin "11") (pinfunction "DQ6_11") (pintype "unspecified"))
    )
    (net (code "144") (name "SD_DQ7") (class "Default")
      (node (ref "U1") (pin "J16") (pinfunction "PR23A_J16") (pintype "unspecified"))
      (node (ref "U5") (pin "13") (pinfunction "DQ7_13") (pintype "unspecified"))
    )
    (net (code "145") (name "SD_DQ8") (class "Default")
      (node (ref "U1") (pin "D16") (pinfunction "PR8A_D16") (pintype "unspecified"))
      (node (ref "U5") (pin "42") (pinfunction "DQ8_42") (pintype "unspecified"))
    )
    (net (code "146") (name "SD_DQ9") (class "Default")
      (node (ref "U1") (pin "E15") (pinfunction "PR8B_E15") (pintype "unspecified"))
      (node (ref "U5") (pin "44") (pinfunction "DQ9_44") (pintype "unspecified"))
    )
    (net (code "147") (name "SD_DQ10") (class "Default")
      (node (ref "U1") (pin "E16") (pinfunction "PR11D_E16") (pintype "unspecified"))
      (node (ref "U5") (pin "45") (pinfunction "DQ10_45") (pintype "unspecified"))
    )
    (net (code "148") (name "SD_DQ11") (class "Default")
      (node (ref "U1") (pin "F15") (pinfunction "PR11C_F15") (pintype "unspecified"))
      (node (ref "U5") (pin "47") (pinfunction "DQ11_47") (pintype "unspecified"))
    )
    (net (code "149") (name "SD_DQ12") (class "Default")
      (node (ref "U1") (pin "F16") (pinfunction "PR14A_F16") (pintype "unspecified"))
      (node (ref "U5") (pin "48") (pinfunction "DQ12_48") (pintype "unspecified"))
    )
    (net (code "150") (name "SD_DQ13") (class "Default")
      (node (ref "U1") (pin "G15") (pinfunction "PR14B_G15") (pintype "unspecified"))
      (node (ref "U5") (pin "50") (pinfunction "DQ13_50") (pintype "unspecified"))
    )
    (net (code "151") (name "SD_DQ14") (class "Default")
      (node (ref "U1") (pin "G16") (pinfunction "PR20A_G16") (pintype "unspecified"))
      (node (ref "U5") (pin "51") (pinfunction "DQ14_51") (pintype "unspecified"))
    )
    (net (code "152") (name "SD_DQ15") (class "Default")
      (node (ref "U1") (pin "H15") (pinfunction "PR20B_H15") (pintype "unspecified"))
      (node (ref "U5") (pin "53") (pinfunction "DQ15_53") (pintype "unspecified"))
    )
    (net (code "153") (name "SD_DQM0") (class "Default")
      (node (ref "R69") (pin "1") (pinfunction "1_1") (pintype "input"))
      (node (ref "U1") (pin "T15") (pinfunction "PR38D_T15") (pintype "unspecified"))
    )
    (net (code "154") (name "SD_DQM1") (class "Default")
      (node (ref "R70") (pin "2") (pinfunction "2_2") (pintype "input"))
      (node (ref "U1") (pin "D14") (pinfunction "PR2D_D14") (pintype "unspecified"))
    )
    (net (code "155") (name "SD_RAS_N") (class "Default")
      (node (ref "R50") (pin "1") (pinfunction "1_1") (pintype "input"))
      (node (ref "U1") (pin "T14") (pinfunction "PR41D_T14") (pintype "unspecified"))
    )
    (net (code "156") (name "SD_WE_N") (class "Default")
      (node (ref "R48") (pin "1") (pinfunction "1_1") (pintype "input"))
      (node (ref "U1") (pin "N13") (pinfunction "PR38A_N13") (pintype "unspecified"))
    )
    (net (code "157") (name "SSPI_CS_N") (class "Default")
      (node (ref "R86") (pin "1") (pinfunction "1_1") (pintype "input"))
      (node (ref "U1") (pin "R1") (pinfunction "PL35B_R1") (pintype "unspecified"))
    )
    (net (code "158") (name "TCK") (class "Default")
      (node (ref "H1") (pin "1") (pinfunction "1_1") (pintype "input"))
      (node (ref "U1") (pin "T10") (pinfunction "TCK_T10") (pintype "unspecified"))
    )
    (net (code "159") (name "TDI") (class "Default")
      (node (ref "H1") (pin "3") (pinfunction "3_3") (pintype "input"))
      (node (ref "U1") (pin "R11") (pinfunction "TDI_R11") (pintype "unspecified"))
    )
    (net (code "160") (name "TDO") (class "Default")
      (node (ref "H1") (pin "4") (pinfunction "4_4") (pintype "input"))
      (node (ref "U1") (pin "M10") (pinfunction "TDO_M10") (pintype "unspecified"))
    )
    (net (code "161") (name "TMS") (class "Default")
      (node (ref "H1") (pin "2") (pinfunction "2_2") (pintype "input"))
      (node (ref "U1") (pin "T11") (pinfunction "TMS_T11") (pintype "unspecified"))
    )
    (net (code "162") (name "TX") (class "Default")
      (node (ref "U1") (pin "K2") (pinfunction "PL23D_K2") (pintype "unspecified"))
      (node (ref "U2") (pin "37") (pinfunction "TXD0_37") (pintype "unspecified"))
    )
    (net (code "163") (name "USB_VBUS") (class "Default")
      (node (ref "R44") (pin "1") (pinfunction "1_1") (pintype "unspecified"))
      (node (ref "R45") (pin "2") (pinfunction "2_2") (pintype "unspecified"))
      (node (ref "U2") (pin "15") (pinfunction "IO3_15") (pintype "unspecified"))
    )
    (net (code "164") (name "VSYNC") (class "Default")
      (node (ref "R73") (pin "1") (pinfunction "1_1") (pintype "input"))
      (node (ref "U1") (pin "B10") (pinfunction "PT44A_B10") (pintype "unspecified"))
    )
    (net (code "165") (name "Y2") (class "Default")
      (node (ref "R82") (pin "1") (pinfunction "1_1") (pintype "input"))
      (node (ref "U1") (pin "B14") (pinfunction "PT67A_B14") (pintype "unspecified"))
    )
    (net (code "166") (name "Y3") (class "Default")
      (node (ref "R84") (pin "1") (pinfunction "1_1") (pintype "input"))
      (node (ref "U1") (pin "C12") (pinfunction "PT56B_C12") (pintype "unspecified"))
    )
    (net (code "167") (name "Y4") (class "Default")
      (node (ref "R85") (pin "1") (pinfunction "1_1") (pintype "input"))
      (node (ref "U1") (pin "C13") (pinfunction "PT60B_C13") (pintype "unspecified"))
    )
    (net (code "168") (name "Y5") (class "Default")
      (node (ref "R83") (pin "1") (pinfunction "1_1") (pintype "input"))
      (node (ref "U1") (pin "A15") (pinfunction "PT67B_A15") (pintype "unspecified"))
    )
    (net (code "169") (name "Y6") (class "Default")
      (node (ref "R81") (pin "1") (pinfunction "1_1") (pintype "input"))
      (node (ref "U1") (pin "A14") (pinfunction "PT65B_A14") (pintype "unspecified"))
    )
    (net (code "170") (name "Y7") (class "Default")
      (node (ref "R79") (pin "1") (pinfunction "1_1") (pintype "input"))
      (node (ref "U1") (pin "A13") (pinfunction "PT65A_A13") (pintype "unspecified"))
    )
    (net (code "171") (name "Y8") (class "Default")
      (node (ref "R78") (pin "1") (pinfunction "1_1") (pintype "input"))
      (node (ref "U1") (pin "B12") (pinfunction "PT56A_B12") (pintype "unspecified"))
    )
    (net (code "172") (name "Y9") (class "Default")
      (node (ref "R76") (pin "1") (pinfunction "1_1") (pintype "input"))
      (node (ref "U1") (pin "B11") (pinfunction "PT49A_B11") (pintype "unspecified"))
    )
    (net (code "173") (name "unconnected-(P1-Pad1)") (class "Default")
      (node (ref "P1") (pin "1") (pinfunction "1_1") (pintype "input+no_connect"))
    )
    (net (code "174") (name "unconnected-(P1-Pad10)") (class "Default")
      (node (ref "P1") (pin "10") (pinfunction "10_10") (pintype "input+no_connect"))
    )
    (net (code "175") (name "unconnected-(SCREW1-Pad1)") (class "Default")
      (node (ref "SCREW1") (pin "1") (pinfunction "1_1") (pintype "input"))
    )
    (net (code "176") (name "unconnected-(SCREW2-Pad1)") (class "Default")
      (node (ref "SCREW2") (pin "1") (pinfunction "1_1") (pintype "input"))
    )
    (net (code "177") (name "unconnected-(SCREW3-Pad1)") (class "Default")
      (node (ref "SCREW3") (pin "1") (pinfunction "1_1") (pintype "input"))
    )
    (net (code "178") (name "unconnected-(SCREW4-Pad1)") (class "Default")
      (node (ref "SCREW4") (pin "1") (pinfunction "1_1") (pintype "input"))
    )
    (net (code "179") (name "unconnected-(U1A-PL2C-PadC3)") (class "Default")
      (node (ref "U1") (pin "C3") (pinfunction "PL2C_C3") (pintype "unspecified"))
    )
    (net (code "180") (name "unconnected-(U1A-PL2D-PadD3)") (class "Default")
      (node (ref "U1") (pin "D3") (pinfunction "PL2D_D3") (pintype "unspecified"))
    )
    (net (code "181") (name "unconnected-(U1A-PL5A-PadC1)") (class "Default")
      (node (ref "U1") (pin "C1") (pinfunction "PL5A_C1") (pintype "unspecified"))
    )
    (net (code "182") (name "unconnected-(U1A-PL5B-PadC2)") (class "Default")
      (node (ref "U1") (pin "C2") (pinfunction "PL5B_C2") (pintype "unspecified"))
    )
    (net (code "183") (name "unconnected-(U1A-PL5C-PadE3)") (class "Default")
      (node (ref "U1") (pin "E3") (pinfunction "PL5C_E3") (pintype "unspecified"))
    )
    (net (code "184") (name "unconnected-(U1A-PL5D-PadF3)") (class "Default")
      (node (ref "U1") (pin "F3") (pinfunction "PL5D_F3") (pintype "unspecified"))
    )
    (net (code "185") (name "unconnected-(U1A-PL8A-PadD1)") (class "Default")
      (node (ref "U1") (pin "D1") (pinfunction "PL8A_D1") (pintype "unspecified"))
    )
    (net (code "186") (name "unconnected-(U1A-PL8C-PadF4)") (class "Default")
      (node (ref "U1") (pin "F4") (pinfunction "PL8C_F4") (pintype "unspecified"))
    )
    (net (code "187") (name "unconnected-(U1A-PL8D-PadF5)") (class "Default")
      (node (ref "U1") (pin "F5") (pinfunction "PL8D_F5") (pintype "unspecified"))
    )
    (net (code "188") (name "unconnected-(U1A-PL11A-PadG5)") (class "Default")
      (node (ref "U1") (pin "G5") (pinfunction "PL11A_G5") (pintype "unspecified"))
    )
    (net (code "189") (name "unconnected-(U1A-PL11B-PadG4)") (class "Default")
      (node (ref "U1") (pin "G4") (pinfunction "PL11B_G4") (pintype "unspecified"))
    )
    (net (code "190") (name "unconnected-(U1A-PL14C-PadG3)") (class "Default")
      (node (ref "U1") (pin "G3") (pinfunction "PL14C_G3") (pintype "unspecified"))
    )
    (net (code "191") (name "unconnected-(U1A-PL14D-PadH3)") (class "Default")
      (node (ref "U1") (pin "H3") (pinfunction "PL14D_H3") (pintype "unspecified"))
    )
    (net (code "192") (name "unconnected-(U1A-PL17A-PadH5)") (class "Default")
      (node (ref "U1") (pin "H5") (pinfunction "PL17A_H5") (pintype "unspecified"))
    )
    (net (code "193") (name "unconnected-(U1A-PL17B-PadH4)") (class "Default")
      (node (ref "U1") (pin "H4") (pinfunction "PL17B_H4") (pintype "unspecified"))
    )
    (net (code "194") (name "unconnected-(U1A-PL20B-PadH2)") (class "Default")
      (node (ref "U1") (pin "H2") (pinfunction "PL20B_H2") (pintype "unspecified"))
    )
    (net (code "195") (name "unconnected-(U1A-PR2A-PadB16)") (class "Default")
      (node (ref "U1") (pin "B16") (pinfunction "PR2A_B16") (pintype "unspecified"))
    )
    (net (code "196") (name "unconnected-(U1A-PR2B-PadB15)") (class "Default")
      (node (ref "U1") (pin "B15") (pinfunction "PR2B_B15") (pintype "unspecified"))
    )
    (net (code "197") (name "unconnected-(U1A-PR2C-PadC14)") (class "Default")
      (node (ref "U1") (pin "C14") (pinfunction "PR2C_C14") (pintype "unspecified"))
    )
    (net (code "198") (name "unconnected-(U1A-PR5A-PadC16)") (class "Default")
      (node (ref "U1") (pin "C16") (pinfunction "PR5A_C16") (pintype "unspecified"))
    )
    (net (code "199") (name "unconnected-(U1A-PR5B-PadC15)") (class "Default")
      (node (ref "U1") (pin "C15") (pinfunction "PR5B_C15") (pintype "unspecified"))
    )
    (net (code "200") (name "unconnected-(U1A-PR5C-PadE14)") (class "Default")
      (node (ref "U1") (pin "E14") (pinfunction "PR5C_E14") (pintype "unspecified"))
    )
    (net (code "201") (name "unconnected-(U1A-PR5D-PadF14)") (class "Default")
      (node (ref "U1") (pin "F14") (pinfunction "PR5D_F14") (pintype "unspecified"))
    )
    (net (code "202") (name "unconnected-(U1A-PR8C-PadF13)") (class "Default")
      (node (ref "U1") (pin "F13") (pinfunction "PR8C_F13") (pintype "unspecified"))
    )
    (net (code "203") (name "unconnected-(U1A-PR8D-PadF12)") (class "Default")
      (node (ref "U1") (pin "F12") (pinfunction "PR8D_F12") (pintype "unspecified"))
    )
    (net (code "204") (name "unconnected-(U1A-PR11A-PadG12)") (class "Default")
      (node (ref "U1") (pin "G12") (pinfunction "PR11A_G12") (pintype "unspecified"))
    )
    (net (code "205") (name "unconnected-(U1A-PR11B-PadG13)") (class "Default")
      (node (ref "U1") (pin "G13") (pinfunction "PR11B_G13") (pintype "unspecified"))
    )
    (net (code "206") (name "unconnected-(U1A-PR14C-PadG14)") (class "Default")
      (node (ref "U1") (pin "G14") (pinfunction "PR14C_G14") (pintype "unspecified"))
    )
    (net (code "207") (name "unconnected-(U1A-PR14D-PadH14)") (class "Default")
      (node (ref "U1") (pin "H14") (pinfunction "PR14D_H14") (pintype "unspecified"))
    )
    (net (code "208") (name "unconnected-(U1A-PR17A-PadH12)") (class "Default")
      (node (ref "U1") (pin "H12") (pinfunction "PR17A_H12") (pintype "unspecified"))
    )
    (net (code "209") (name "unconnected-(U1A-PR17B-PadH13)") (class "Default")
      (node (ref "U1") (pin "H13") (pinfunction "PR17B_H13") (pintype "unspecified"))
    )
    (net (code "210") (name "unconnected-(U1A-PT4B-PadB3)") (class "Default")
      (node (ref "U1") (pin "B3") (pinfunction "PT4B_B3") (pintype "unspecified"))
    )
    (net (code "211") (name "unconnected-(U1A-PT9A-PadE4)") (class "Default")
      (node (ref "U1") (pin "E4") (pinfunction "PT9A_E4") (pintype "unspecified"))
    )
    (net (code "212") (name "unconnected-(U1A-PT9B-PadD4)") (class "Default")
      (node (ref "U1") (pin "D4") (pinfunction "PT9B_D4") (pintype "unspecified"))
    )
    (net (code "213") (name "unconnected-(U1A-PT11A-PadC4)") (class "Default")
      (node (ref "U1") (pin "C4") (pinfunction "PT11A_C4") (pintype "unspecified"))
    )
    (net (code "214") (name "unconnected-(U1A-PT13A-PadE5)") (class "Default")
      (node (ref "U1") (pin "E5") (pinfunction "PT13A_E5") (pintype "unspecified"))
    )
    (net (code "215") (name "unconnected-(U1A-PT13B-PadD5)") (class "Default")
      (node (ref "U1") (pin "D5") (pinfunction "PT13B_D5") (pintype "unspecified"))
    )
    (net (code "216") (name "unconnected-(U1A-PT15A-PadC5)") (class "Default")
      (node (ref "U1") (pin "C5") (pinfunction "PT15A_C5") (pintype "unspecified"))
    )
    (net (code "217") (name "unconnected-(U1A-PT20A-PadE6)") (class "Default")
      (node (ref "U1") (pin "E6") (pinfunction "PT20A_E6") (pintype "unspecified"))
    )
    (net (code "218") (name "unconnected-(U1A-PT20B-PadD6)") (class "Default")
      (node (ref "U1") (pin "D6") (pinfunction "PT20B_D6") (pintype "unspecified"))
    )
    (net (code "219") (name "unconnected-(U1A-PT22A-PadC6)") (class "Default")
      (node (ref "U1") (pin "C6") (pinfunction "PT22A_C6") (pintype "unspecified"))
    )
    (net (code "220") (name "unconnected-(U1A-PT24A-PadE7)") (class "Default")
      (node (ref "U1") (pin "E7") (pinfunction "PT24A_E7") (pintype "unspecified"))
    )
    (net (code "221") (name "unconnected-(U1A-PT24B-PadD7)") (class "Default")
      (node (ref "U1") (pin "D7") (pinfunction "PT24B_D7") (pintype "unspecified"))
    )
    (net (code "222") (name "unconnected-(U1A-PT33A-PadE8)") (class "Default")
      (node (ref "U1") (pin "E8") (pinfunction "PT33A_E8") (pintype "unspecified"))
    )
    (net (code "223") (name "unconnected-(U1A-PT33B-PadD8)") (class "Default")
      (node (ref "U1") (pin "D8") (pinfunction "PT33B_D8") (pintype "unspecified"))
    )
    (net (code "224") (name "unconnected-(U1A-PT35B-PadB8)") (class "Default")
      (node (ref "U1") (pin "B8") (pinfunction "PT35B_B8") (pintype "unspecified"))
    )
    (net (code "225") (name "unconnected-(U1A-PT38B-PadC9)") (class "Default")
      (node (ref "U1") (pin "C9") (pinfunction "PT38B_C9") (pintype "unspecified"))
    )
    (net (code "226") (name "unconnected-(U1A-PT40A-PadD9)") (class "Default")
      (node (ref "U1") (pin "D9") (pinfunction "PT40A_D9") (pintype "unspecified"))
    )
    (net (code "227") (name "unconnected-(U1A-PT40B-PadE9)") (class "Default")
      (node (ref "U1") (pin "E9") (pinfunction "PT40B_E9") (pintype "unspecified"))
    )
    (net (code "228") (name "unconnected-(U1A-PT42A-PadA9)") (class "Default")
      (node (ref "U1") (pin "A9") (pinfunction "PT42A_A9") (pintype "unspecified"))
    )
    (net (code "229") (name "unconnected-(U1A-PT44B-PadC10)") (class "Default")
      (node (ref "U1") (pin "C10") (pinfunction "PT44B_C10") (pintype "unspecified"))
    )
    (net (code "230") (name "unconnected-(U1A-PT47A-PadD10)") (class "Default")
      (node (ref "U1") (pin "D10") (pinfunction "PT47A_D10") (pintype "unspecified"))
    )
    (net (code "231") (name "unconnected-(U1A-PT47B-PadE10)") (class "Default")
      (node (ref "U1") (pin "E10") (pinfunction "PT47B_E10") (pintype "unspecified"))
    )
    (net (code "232") (name "unconnected-(U1A-PT49B-PadC11)") (class "Default")
      (node (ref "U1") (pin "C11") (pinfunction "PT49B_C11") (pintype "unspecified"))
    )
    (net (code "233") (name "unconnected-(U1A-PT51A-PadD11)") (class "Default")
      (node (ref "U1") (pin "D11") (pinfunction "PT51A_D11") (pintype "unspecified"))
    )
    (net (code "234") (name "unconnected-(U1A-PT51B-PadE11)") (class "Default")
      (node (ref "U1") (pin "E11") (pinfunction "PT51B_E11") (pintype "unspecified"))
    )
    (net (code "235") (name "unconnected-(U1A-PT58A-PadD12)") (class "Default")
      (node (ref "U1") (pin "D12") (pinfunction "PT58A_D12") (pintype "unspecified"))
    )
    (net (code "236") (name "unconnected-(U1A-PT58B-PadE12)") (class "Default")
      (node (ref "U1") (pin "E12") (pinfunction "PT58B_E12") (pintype "unspecified"))
    )
    (net (code "237") (name "unconnected-(U1A-PT60A-PadB13)") (class "Default")
      (node (ref "U1") (pin "B13") (pinfunction "PT60A_B13") (pintype "unspecified"))
    )
    (net (code "238") (name "unconnected-(U1A-PT62A-PadD13)") (class "Default")
      (node (ref "U1") (pin "D13") (pinfunction "PT62A_D13") (pintype "unspecified"))
    )
    (net (code "239") (name "unconnected-(U1A-PT62B-PadE13)") (class "Default")
      (node (ref "U1") (pin "E13") (pinfunction "PT62B_E13") (pintype "unspecified"))
    )
    (net (code "240") (name "unconnected-(U1B-PB4B-PadR6)") (class "Default")
      (node (ref "U1") (pin "R6") (pinfunction "PB4B_R6") (pintype "unspecified"))
    )
    (net (code "241") (name "unconnected-(U1B-PB6A-PadR7)") (class "Default")
      (node (ref "U1") (pin "R7") (pinfunction "PB6A_R7") (pintype "unspecified"))
    )
    (net (code "242") (name "unconnected-(U1B-PB6B-PadP7)") (class "Default")
      (node (ref "U1") (pin "P7") (pinfunction "PB6B_P7") (pintype "unspecified"))
    )
    (net (code "243") (name "unconnected-(U1B-PB9A-PadN7)") (class "Default")
      (node (ref "U1") (pin "N7") (pinfunction "PB9A_N7") (pintype "unspecified"))
    )
    (net (code "244") (name "unconnected-(U1B-PB9B-PadM7)") (class "Default")
      (node (ref "U1") (pin "M7") (pinfunction "PB9B_M7") (pintype "unspecified"))
    )
    (net (code "245") (name "unconnected-(U1B-PB13A-PadR8)") (class "Default")
      (node (ref "U1") (pin "R8") (pinfunction "PB13A_R8") (pintype "unspecified"))
    )
    (net (code "246") (name "unconnected-(U1B-PB13B-PadP8)") (class "Default")
      (node (ref "U1") (pin "P8") (pinfunction "PB13B_P8") (pintype "unspecified"))
    )
    (net (code "247") (name "unconnected-(U1B-PB15A-PadN8)") (class "Default")
      (node (ref "U1") (pin "N8") (pinfunction "PB15A_N8") (pintype "unspecified"))
    )
    (net (code "248") (name "unconnected-(U1B-PB18A-PadM9)") (class "Default")
      (node (ref "U1") (pin "M9") (pinfunction "PB18A_M9") (pintype "unspecified"))
    )
    (net (code "249") (name "unconnected-(U1B-PL17C-PadJ4)") (class "Default")
      (node (ref "U1") (pin "J4") (pinfunction "PL17C_J4") (pintype "unspecified"))
    )
    (net (code "250") (name "unconnected-(U1B-PL17D-PadJ5)") (class "Default")
      (node (ref "U1") (pin "J5") (pinfunction "PL17D_J5") (pintype "unspecified"))
    )
    (net (code "251") (name "unconnected-(U1B-PL20C-PadJ3)") (class "Default")
      (node (ref "U1") (pin "J3") (pinfunction "PL20C_J3") (pintype "unspecified"))
    )
    (net (code "252") (name "unconnected-(U1B-PL20D-PadK3)") (class "Default")
      (node (ref "U1") (pin "K3") (pinfunction "PL20D_K3") (pintype "unspecified"))
    )
    (net (code "253") (name "unconnected-(U1B-PL26A-PadL1)") (class "Default")
      (node (ref "U1") (pin "L1") (pinfunction "PL26A_L1") (pintype "unspecified"))
    )
    (net (code "254") (name "unconnected-(U1B-PL26B-PadL2)") (class "Default")
      (node (ref "U1") (pin "L2") (pinfunction "PL26B_L2") (pintype "unspecified"))
    )
    (net (code "255") (name "unconnected-(U1B-PL26D-PadM2)") (class "Default")
      (node (ref "U1") (pin "M2") (pinfunction "PL26D_M2") (pintype "unspecified"))
    )
    (net (code "256") (name "unconnected-(U1B-PL29A-PadK4)") (class "Default")
      (node (ref "U1") (pin "K4") (pinfunction "PL29A_K4") (pintype "unspecified"))
    )
    (net (code "257") (name "unconnected-(U1B-PL29B-PadK5)") (class "Default")
      (node (ref "U1") (pin "K5") (pinfunction "PL29B_K5") (pintype "unspecified"))
    )
    (net (code "258") (name "unconnected-(U1B-PL29C-PadL4)") (class "Default")
      (node (ref "U1") (pin "L4") (pinfunction "PL29C_L4") (pintype "unspecified"))
    )
    (net (code "259") (name "unconnected-(U1B-PL29D-PadL5)") (class "Default")
      (node (ref "U1") (pin "L5") (pinfunction "PL29D_L5") (pintype "unspecified"))
    )
    (net (code "260") (name "unconnected-(U1B-PL32A-PadN1)") (class "Default")
      (node (ref "U1") (pin "N1") (pinfunction "PL32A_N1") (pintype "unspecified"))
    )
    (net (code "261") (name "unconnected-(U1B-PL32C-PadL3)") (class "Default")
      (node (ref "U1") (pin "L3") (pinfunction "PL32C_L3") (pintype "unspecified"))
    )
    (net (code "262") (name "unconnected-(U1B-PL32D-PadM3)") (class "Default")
      (node (ref "U1") (pin "M3") (pinfunction "PL32D_M3") (pintype "unspecified"))
    )
    (net (code "263") (name "unconnected-(U1B-PL35C-PadM4)") (class "Default")
      (node (ref "U1") (pin "M4") (pinfunction "PL35C_M4") (pintype "unspecified"))
    )
    (net (code "264") (name "unconnected-(U1B-PL35D-PadN3)") (class "Default")
      (node (ref "U1") (pin "N3") (pinfunction "PL35D_N3") (pintype "unspecified"))
    )
    (net (code "265") (name "unconnected-(U1B-PL38A-PadN4)") (class "Default")
      (node (ref "U1") (pin "N4") (pinfunction "PL38A_N4") (pintype "unspecified"))
    )
    (net (code "266") (name "unconnected-(U1B-PL38C-PadR2)") (class "Default")
      (node (ref "U1") (pin "R2") (pinfunction "PL38C_R2") (pintype "unspecified"))
    )
    (net (code "267") (name "unconnected-(U1B-PL41B-PadR3)") (class "Default")
      (node (ref "U1") (pin "R3") (pinfunction "PL41B_R3") (pintype "unspecified"))
    )
    (net (code "268") (name "unconnected-(U1B-PL41C-PadR4)") (class "Default")
      (node (ref "U1") (pin "R4") (pinfunction "PL41C_R4") (pintype "unspecified"))
    )
    (net (code "269") (name "unconnected-(U1B-PL44A-PadR5)") (class "Default")
      (node (ref "U1") (pin "R5") (pinfunction "PL44A_R5") (pintype "unspecified"))
    )
    (net (code "270") (name "unconnected-(U1B-PL44C-PadM5)") (class "Default")
      (node (ref "U1") (pin "M5") (pinfunction "PL44C_M5") (pintype "unspecified"))
    )
    (net (code "271") (name "unconnected-(U1B-PL44D-PadN5)") (class "Default")
      (node (ref "U1") (pin "N5") (pinfunction "PL44D_N5") (pintype "unspecified"))
    )
    (net (code "272") (name "unconnected-(U1B-PL47A-PadM6)") (class "Default")
      (node (ref "U1") (pin "M6") (pinfunction "PL47A_M6") (pintype "unspecified"))
    )
    (net (code "273") (name "unconnected-(U1B-PL47B-PadN6)") (class "Default")
      (node (ref "U1") (pin "N6") (pinfunction "PL47B_N6") (pintype "unspecified"))
    )
    (net (code "274") (name "unconnected-(U1B-PL47C-PadP6)") (class "Default")
      (node (ref "U1") (pin "P6") (pinfunction "PL47C_P6") (pintype "unspecified"))
    )
    (net (code "275") (name "unconnected-(U1B-PR17C-PadJ13)") (class "Default")
      (node (ref "U1") (pin "J13") (pinfunction "PR17C_J13") (pintype "unspecified"))
    )
    (net (code "276") (name "unconnected-(U1B-PR17D-PadJ12)") (class "Default")
      (node (ref "U1") (pin "J12") (pinfunction "PR17D_J12") (pintype "unspecified"))
    )
    (net (code "277") (name "unconnected-(U1B-PR20C-PadJ14)") (class "Default")
      (node (ref "U1") (pin "J14") (pinfunction "PR20C_J14") (pintype "unspecified"))
    )
    (net (code "278") (name "unconnected-(U1B-PR20D-PadK14)") (class "Default")
      (node (ref "U1") (pin "K14") (pinfunction "PR20D_K14") (pintype "unspecified"))
    )
    (net (code "279") (name "unconnected-(U1B-PR23D-PadK15)") (class "Default")
      (node (ref "U1") (pin "K15") (pinfunction "PR23D_K15") (pintype "unspecified"))
    )
    (net (code "280") (name "unconnected-(U1B-PR26A-PadL16)") (class "Default")
      (node (ref "U1") (pin "L16") (pinfunction "PR26A_L16") (pintype "unspecified"))
    )
    (net (code "281") (name "unconnected-(U1B-PR29A-PadK13)") (class "Default")
      (node (ref "U1") (pin "K13") (pinfunction "PR29A_K13") (pintype "unspecified"))
    )
    (net (code "282") (name "unconnected-(U1B-PR29C-PadL13)") (class "Default")
      (node (ref "U1") (pin "L13") (pinfunction "PR29C_L13") (pintype "unspecified"))
    )
    (net (code "283") (name "unconnected-(U1B-PR32A-PadN16)") (class "Default")
      (node (ref "U1") (pin "N16") (pinfunction "PR32A_N16") (pintype "unspecified"))
    )
    (net (code "284") (name "unconnected-(U1B-PR32B-PadP15)") (class "Default")
      (node (ref "U1") (pin "P15") (pinfunction "PR32B_P15") (pintype "unspecified"))
    )
    (net (code "285") (name "unconnected-(U1B-PR32C-PadL14)") (class "Default")
      (node (ref "U1") (pin "L14") (pinfunction "PR32C_L14") (pintype "unspecified"))
    )
    (net (code "286") (name "unconnected-(U1B-PR35C-PadM13)") (class "Default")
      (node (ref "U1") (pin "M13") (pinfunction "PR35C_M13") (pintype "unspecified"))
    )
    (net (code "287") (name "unconnected-(U1B-PR35D-PadN14)") (class "Default")
      (node (ref "U1") (pin "N14") (pinfunction "PR35D_N14") (pintype "unspecified"))
    )
    (net (code "288") (name "unconnected-(U1B-PR38B-PadP14)") (class "Default")
      (node (ref "U1") (pin "P14") (pinfunction "PR38B_P14") (pintype "unspecified"))
    )
    (net (code "289") (name "unconnected-(U1B-PR41A-PadP13)") (class "Default")
      (node (ref "U1") (pin "P13") (pinfunction "PR41A_P13") (pintype "unspecified"))
    )
    (net (code "290") (name "unconnected-(U1B-PR41B-PadR14)") (class "Default")
      (node (ref "U1") (pin "R14") (pinfunction "PR41B_R14") (pintype "unspecified"))
    )
    (net (code "291") (name "unconnected-(U1B-PR44A-PadR12)") (class "Default")
      (node (ref "U1") (pin "R12") (pinfunction "PR44A_R12") (pintype "unspecified"))
    )
    (net (code "292") (name "unconnected-(U1B-PR44B-PadT13)") (class "Default")
      (node (ref "U1") (pin "T13") (pinfunction "PR44B_T13") (pintype "unspecified"))
    )
    (net (code "293") (name "unconnected-(U1B-PR44C-PadM12)") (class "Default")
      (node (ref "U1") (pin "M12") (pinfunction "PR44C_M12") (pintype "unspecified"))
    )
    (net (code "294") (name "unconnected-(U1B-PR44D-PadN12)") (class "Default")
      (node (ref "U1") (pin "N12") (pinfunction "PR44D_N12") (pintype "unspecified"))
    )
    (net (code "295") (name "unconnected-(U1B-PR47A-PadM11)") (class "Default")
      (node (ref "U1") (pin "M11") (pinfunction "PR47A_M11") (pintype "unspecified"))
    )
    (net (code "296") (name "unconnected-(U1B-PR47B-PadN11)") (class "Default")
      (node (ref "U1") (pin "N11") (pinfunction "PR47B_N11") (pintype "unspecified"))
    )
    (net (code "297") (name "unconnected-(U1B-PR47C-PadP11)") (class "Default")
      (node (ref "U1") (pin "P11") (pinfunction "PR47C_P11") (pintype "unspecified"))
    )
    (net (code "298") (name "unconnected-(U1B-PR47D-PadP12)") (class "Default")
      (node (ref "U1") (pin "P12") (pinfunction "PR47D_P12") (pintype "unspecified"))
    )
    (net (code "299") (name "unconnected-(U2-IO1-Pad39)") (class "Default")
      (node (ref "U2") (pin "39") (pinfunction "IO1_39") (pintype "unspecified"))
    )
    (net (code "300") (name "unconnected-(U2-IO2-Pad38)") (class "Default")
      (node (ref "U2") (pin "38") (pinfunction "IO2_38") (pintype "unspecified"))
    )
    (net (code "301") (name "unconnected-(U2-IO4-Pad4)") (class "Default")
      (node (ref "U2") (pin "4") (pinfunction "IO4_4") (pintype "unspecified+no_connect"))
    )
    (net (code "302") (name "unconnected-(U2-IO35-Pad28)") (class "Default")
      (node (ref "U2") (pin "28") (pinfunction "IO35_28") (pintype "unspecified+no_connect"))
    )
    (net (code "303") (name "unconnected-(U2-IO36-Pad29)") (class "Default")
      (node (ref "U2") (pin "29") (pinfunction "IO36_29") (pintype "unspecified+no_connect"))
    )
    (net (code "304") (name "unconnected-(U2-IO37-Pad30)") (class "Default")
      (node (ref "U2") (pin "30") (pinfunction "IO37_30") (pintype "unspecified+no_connect"))
    )
    (net (code "305") (name "unconnected-(U2-IO39-Pad32)") (class "Default")
      (node (ref "U2") (pin "32") (pinfunction "IO39_32") (pintype "unspecified+no_connect"))
    )
    (net (code "306") (name "unconnected-(U2-IO40-Pad33)") (class "Default")
      (node (ref "U2") (pin "33") (pinfunction "IO40_33") (pintype "unspecified+no_connect"))
    )
    (net (code "307") (name "unconnected-(U2-IO41-Pad34)") (class "Default")
      (node (ref "U2") (pin "34") (pinfunction "IO41_34") (pintype "unspecified+no_connect"))
    )
    (net (code "308") (name "unconnected-(U2-IO42-Pad35)") (class "Default")
      (node (ref "U2") (pin "35") (pinfunction "IO42_35") (pintype "unspecified+no_connect"))
    )
    (net (code "309") (name "unconnected-(U2-IO45-Pad26)") (class "Default")
      (node (ref "U2") (pin "26") (pinfunction "IO45_26") (pintype "unspecified+no_connect"))
    )
    (net (code "310") (name "unconnected-(U2-IO46-Pad16)") (class "Default")
      (node (ref "U2") (pin "16") (pinfunction "IO46_16") (pintype "unspecified+no_connect"))
    )
    (net (code "311") (name "unconnected-(U5-NC-Pad40)") (class "Default")
      (node (ref "U5") (pin "40") (pinfunction "NC_40") (pintype "unspecified+no_connect"))
    )
    (net (code "312") (name "unconnected-(U8-TAB-Pad4)") (class "Default")
      (node (ref "U8") (pin "4") (pinfunction "TAB_4") (pintype "unspecified+no_connect"))
    )
    (net (code "313") (name "unconnected-(USB1-DN1-PadA7)") (class "Default")
      (node (ref "USB1") (pin "A7") (pinfunction "DN1_A7") (pintype "unspecified"))
    )
    (net (code "314") (name "unconnected-(USB1-DN2-PadB7)") (class "Default")
      (node (ref "USB1") (pin "B7") (pinfunction "DN2_B7") (pintype "unspecified+no_connect"))
    )
    (net (code "315") (name "unconnected-(USB1-DP1-PadA6)") (class "Default")
      (node (ref "USB1") (pin "A6") (pinfunction "DP1_A6") (pintype "unspecified"))
    )
    (net (code "316") (name "unconnected-(USB1-DP2-PadB6)") (class "Default")
      (node (ref "USB1") (pin "B6") (pinfunction "DP2_B6") (pintype "unspecified+no_connect"))
    )
    (net (code "317") (name "unconnected-(USB1-SBU1-PadA8)") (class "Default")
      (node (ref "USB1") (pin "A8") (pinfunction "SBU1_A8") (pintype "unspecified+no_connect"))
    )
    (net (code "318") (name "unconnected-(USB1-SBU2-PadB8)") (class "Default")
      (node (ref "USB1") (pin "B8") (pinfunction "SBU2_B8") (pintype "unspecified+no_connect"))
    )
    (net (code "319") (name "unconnected-(USB2-DN2-PadB7)") (class "Default")
      (node (ref "USB2") (pin "B7") (pinfunction "DN2_B7") (pintype "unspecified+no_connect"))
    )
    (net (code "320") (name "unconnected-(USB2-DP2-PadB6)") (class "Default")
      (node (ref "USB2") (pin "B6") (pinfunction "DP2_B6") (pintype "unspecified+no_connect"))
    )
    (net (code "321") (name "unconnected-(USB2-SBU1-PadA8)") (class "Default")
      (node (ref "USB2") (pin "A8") (pinfunction "SBU1_A8") (pintype "unspecified+no_connect"))
    )
    (net (code "322") (name "unconnected-(USB2-SBU2-PadB8)") (class "Default")
      (node (ref "USB2") (pin "B8") (pinfunction "SBU2_B8") (pintype "unspecified+no_connect"))
    )
  )
)
